# Precision_Singleboard_Charlieplex.net
KiCad netlist of a schematic drawn in EAGLE
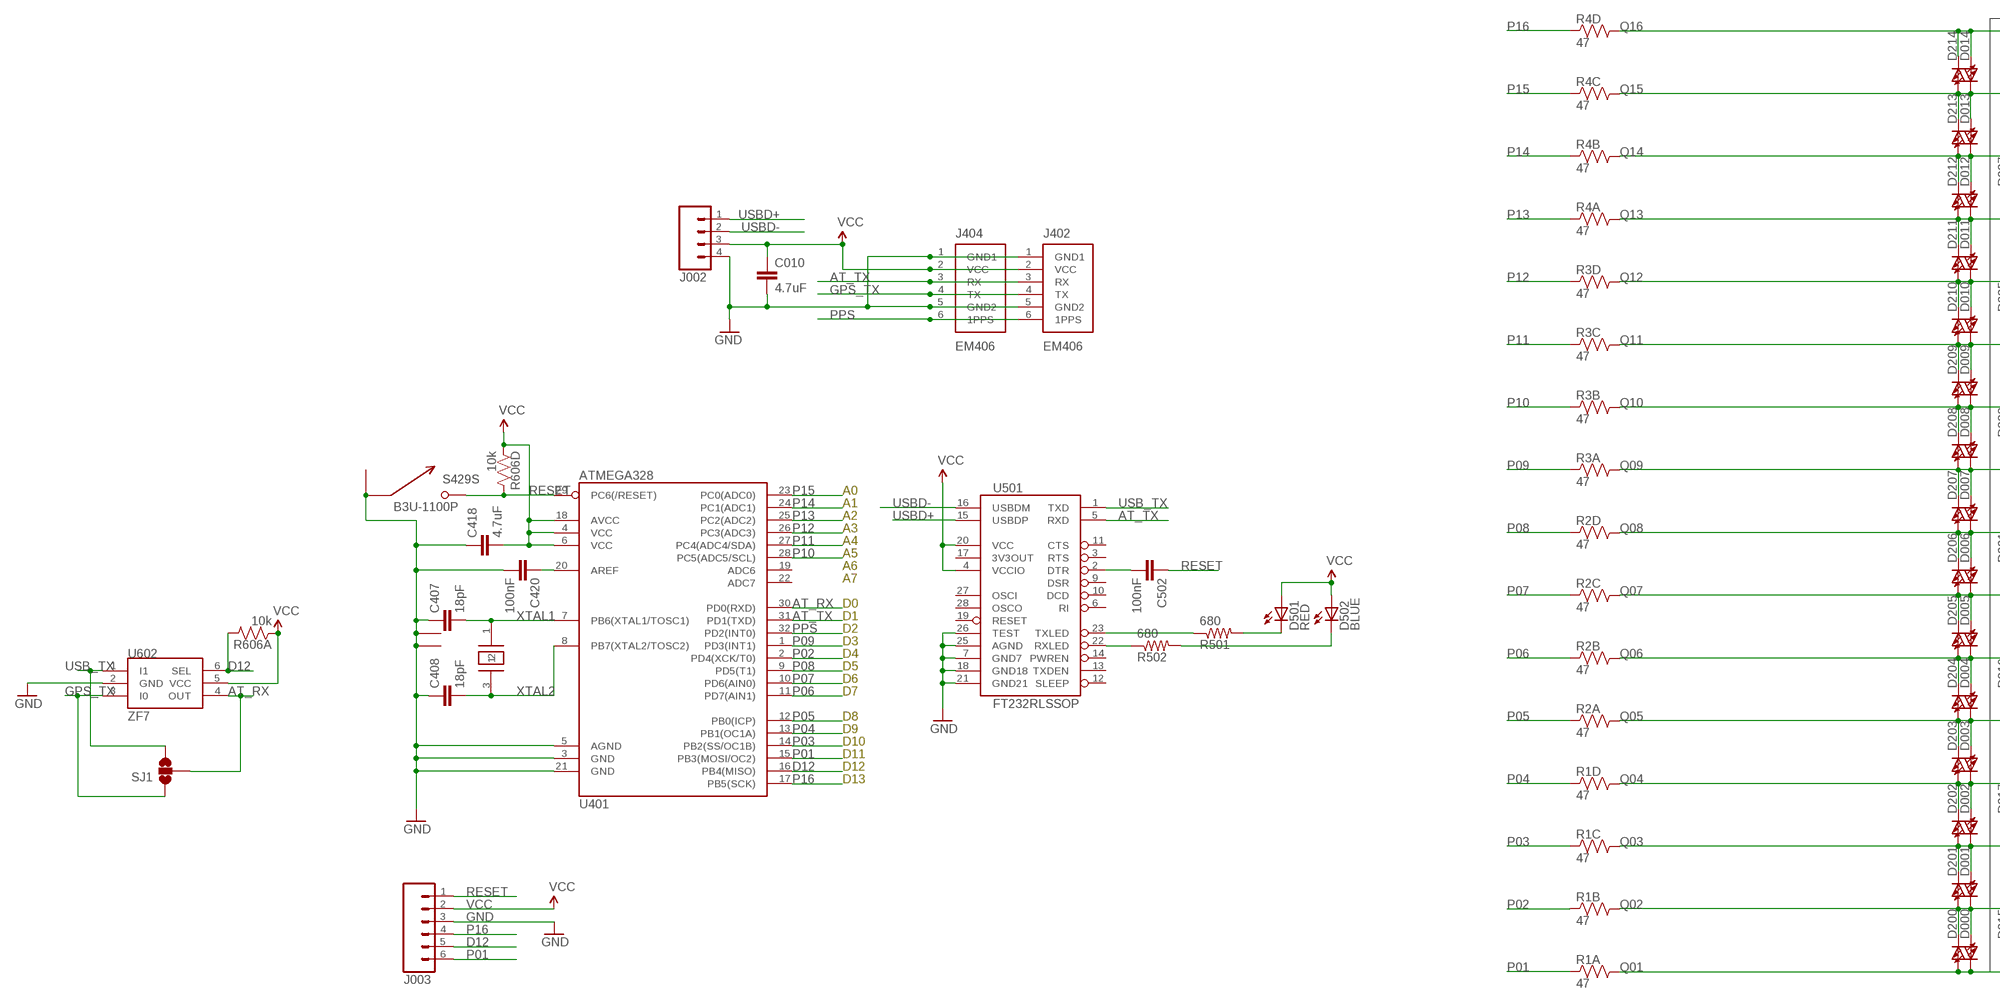
[diagram p0: schematic, sheet 1, part 1 of 2]
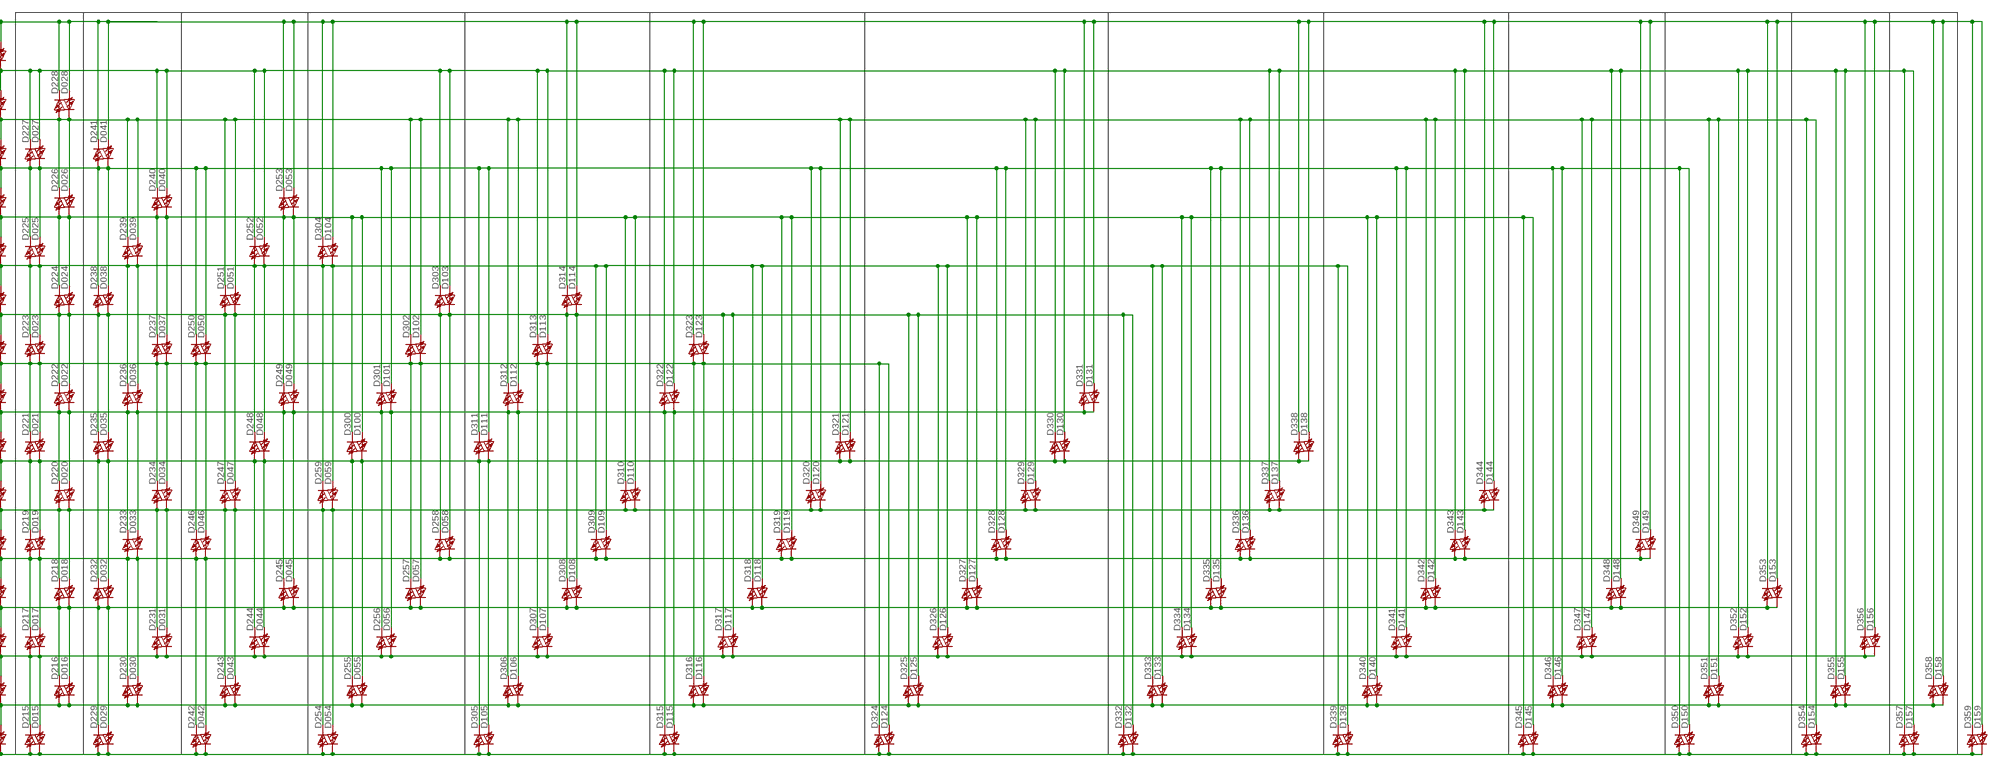
[diagram p1: schematic, sheet 1, part 2 of 2]

(export (version "E")
  (design (tool "Eeschema 10.0.6"))
  (components
    (comp (ref "C010")
      (value "4.7uF")
      (footprint "eagle-import:0603-CAP")
      (libsource (lib "eagle-import") (part "CAP0603-CAP"))
    )
    (comp (ref "C407")
      (value "18pF")
      (footprint "eagle-import:0603-CAP")
      (libsource (lib "eagle-import") (part "CAP0603-CAP"))
    )
    (comp (ref "C408")
      (value "18pF")
      (footprint "eagle-import:0603-CAP")
      (libsource (lib "eagle-import") (part "CAP0603-CAP"))
    )
    (comp (ref "C418")
      (value "4.7uF")
      (footprint "eagle-import:0603-CAP")
      (libsource (lib "eagle-import") (part "CAP0603-CAP"))
    )
    (comp (ref "C420")
      (value "100nF")
      (footprint "eagle-import:0603-CAP")
      (libsource (lib "eagle-import") (part "CAP0603-CAP"))
    )
    (comp (ref "C502")
      (value "100nF")
      (footprint "eagle-import:0603-CAP")
      (libsource (lib "eagle-import") (part "CAP0603-CAP"))
    )
    (comp (ref "D000")
      (value "HOUR")
      (footprint "eagle-import:LED-0603")
      (libsource (lib "eagle-import") (part "LED0603"))
    )
    (comp (ref "D001")
      (value "HOUR")
      (footprint "eagle-import:LED-0603")
      (libsource (lib "eagle-import") (part "LED0603"))
    )
    (comp (ref "D002")
      (value "HOUR")
      (footprint "eagle-import:LED-0603")
      (libsource (lib "eagle-import") (part "LED0603"))
    )
    (comp (ref "D003")
      (value "HOUR")
      (footprint "eagle-import:LED-0603")
      (libsource (lib "eagle-import") (part "LED0603"))
    )
    (comp (ref "D004")
      (value "HOUR")
      (footprint "eagle-import:LED-0603")
      (libsource (lib "eagle-import") (part "LED0603"))
    )
    (comp (ref "D005")
      (value "HOUR")
      (footprint "eagle-import:LED-0603")
      (libsource (lib "eagle-import") (part "LED0603"))
    )
    (comp (ref "D006")
      (value "HOUR")
      (footprint "eagle-import:LED-0603")
      (libsource (lib "eagle-import") (part "LED0603"))
    )
    (comp (ref "D007")
      (value "HOUR")
      (footprint "eagle-import:LED-0603")
      (libsource (lib "eagle-import") (part "LED0603"))
    )
    (comp (ref "D008")
      (value "HOUR")
      (footprint "eagle-import:LED-0603")
      (libsource (lib "eagle-import") (part "LED0603"))
    )
    (comp (ref "D009")
      (value "HOUR")
      (footprint "eagle-import:LED-0603")
      (libsource (lib "eagle-import") (part "LED0603"))
    )
    (comp (ref "D010")
      (value "HOUR")
      (footprint "eagle-import:LED-0603")
      (libsource (lib "eagle-import") (part "LED0603"))
    )
    (comp (ref "D011")
      (value "HOUR")
      (footprint "eagle-import:LED-0603")
      (libsource (lib "eagle-import") (part "LED0603"))
    )
    (comp (ref "D012")
      (value "HOUR")
      (footprint "eagle-import:LED-0603")
      (libsource (lib "eagle-import") (part "LED0603"))
    )
    (comp (ref "D013")
      (value "HOUR")
      (footprint "eagle-import:LED-0603")
      (libsource (lib "eagle-import") (part "LED0603"))
    )
    (comp (ref "D014")
      (value "HOUR")
      (footprint "eagle-import:LED-0603")
      (libsource (lib "eagle-import") (part "LED0603"))
    )
    (comp (ref "D015")
      (value "HOUR")
      (footprint "eagle-import:LED-0603")
      (libsource (lib "eagle-import") (part "LED0603"))
    )
    (comp (ref "D016")
      (value "HOUR")
      (footprint "eagle-import:LED-0603")
      (libsource (lib "eagle-import") (part "LED0603"))
    )
    (comp (ref "D017")
      (value "HOUR")
      (footprint "eagle-import:LED-0603")
      (libsource (lib "eagle-import") (part "LED0603"))
    )
    (comp (ref "D018")
      (value "HOUR")
      (footprint "eagle-import:LED-0603")
      (libsource (lib "eagle-import") (part "LED0603"))
    )
    (comp (ref "D019")
      (value "HOUR")
      (footprint "eagle-import:LED-0603")
      (libsource (lib "eagle-import") (part "LED0603"))
    )
    (comp (ref "D020")
      (value "HOUR")
      (footprint "eagle-import:LED-0603")
      (libsource (lib "eagle-import") (part "LED0603"))
    )
    (comp (ref "D021")
      (value "HOUR")
      (footprint "eagle-import:LED-0603")
      (libsource (lib "eagle-import") (part "LED0603"))
    )
    (comp (ref "D022")
      (value "HOUR")
      (footprint "eagle-import:LED-0603")
      (libsource (lib "eagle-import") (part "LED0603"))
    )
    (comp (ref "D023")
      (value "HOUR")
      (footprint "eagle-import:LED-0603")
      (libsource (lib "eagle-import") (part "LED0603"))
    )
    (comp (ref "D024")
      (value "HOUR")
      (footprint "eagle-import:LED-0603")
      (libsource (lib "eagle-import") (part "LED0603"))
    )
    (comp (ref "D025")
      (value "HOUR")
      (footprint "eagle-import:LED-0603")
      (libsource (lib "eagle-import") (part "LED0603"))
    )
    (comp (ref "D026")
      (value "HOUR")
      (footprint "eagle-import:LED-0603")
      (libsource (lib "eagle-import") (part "LED0603"))
    )
    (comp (ref "D027")
      (value "HOUR")
      (footprint "eagle-import:LED-0603")
      (libsource (lib "eagle-import") (part "LED0603"))
    )
    (comp (ref "D028")
      (value "HOUR")
      (footprint "eagle-import:LED-0603")
      (libsource (lib "eagle-import") (part "LED0603"))
    )
    (comp (ref "D029")
      (value "HOUR")
      (footprint "eagle-import:LED-0603")
      (libsource (lib "eagle-import") (part "LED0603"))
    )
    (comp (ref "D030")
      (value "HOUR")
      (footprint "eagle-import:LED-0603")
      (libsource (lib "eagle-import") (part "LED0603"))
    )
    (comp (ref "D031")
      (value "HOUR")
      (footprint "eagle-import:LED-0603")
      (libsource (lib "eagle-import") (part "LED0603"))
    )
    (comp (ref "D032")
      (value "HOUR")
      (footprint "eagle-import:LED-0603")
      (libsource (lib "eagle-import") (part "LED0603"))
    )
    (comp (ref "D033")
      (value "HOUR")
      (footprint "eagle-import:LED-0603")
      (libsource (lib "eagle-import") (part "LED0603"))
    )
    (comp (ref "D034")
      (value "HOUR")
      (footprint "eagle-import:LED-0603")
      (libsource (lib "eagle-import") (part "LED0603"))
    )
    (comp (ref "D035")
      (value "HOUR")
      (footprint "eagle-import:LED-0603")
      (libsource (lib "eagle-import") (part "LED0603"))
    )
    (comp (ref "D036")
      (value "HOUR")
      (footprint "eagle-import:LED-0603")
      (libsource (lib "eagle-import") (part "LED0603"))
    )
    (comp (ref "D037")
      (value "HOUR")
      (footprint "eagle-import:LED-0603")
      (libsource (lib "eagle-import") (part "LED0603"))
    )
    (comp (ref "D038")
      (value "HOUR")
      (footprint "eagle-import:LED-0603")
      (libsource (lib "eagle-import") (part "LED0603"))
    )
    (comp (ref "D039")
      (value "HOUR")
      (footprint "eagle-import:LED-0603")
      (libsource (lib "eagle-import") (part "LED0603"))
    )
    (comp (ref "D040")
      (value "HOUR")
      (footprint "eagle-import:LED-0603")
      (libsource (lib "eagle-import") (part "LED0603"))
    )
    (comp (ref "D041")
      (value "HOUR")
      (footprint "eagle-import:LED-0603")
      (libsource (lib "eagle-import") (part "LED0603"))
    )
    (comp (ref "D042")
      (value "HOUR")
      (footprint "eagle-import:LED-0603")
      (libsource (lib "eagle-import") (part "LED0603"))
    )
    (comp (ref "D043")
      (value "HOUR")
      (footprint "eagle-import:LED-0603")
      (libsource (lib "eagle-import") (part "LED0603"))
    )
    (comp (ref "D044")
      (value "HOUR")
      (footprint "eagle-import:LED-0603")
      (libsource (lib "eagle-import") (part "LED0603"))
    )
    (comp (ref "D045")
      (value "HOUR")
      (footprint "eagle-import:LED-0603")
      (libsource (lib "eagle-import") (part "LED0603"))
    )
    (comp (ref "D046")
      (value "HOUR")
      (footprint "eagle-import:LED-0603")
      (libsource (lib "eagle-import") (part "LED0603"))
    )
    (comp (ref "D047")
      (value "HOUR")
      (footprint "eagle-import:LED-0603")
      (libsource (lib "eagle-import") (part "LED0603"))
    )
    (comp (ref "D048")
      (value "HOUR")
      (footprint "eagle-import:LED-0603")
      (libsource (lib "eagle-import") (part "LED0603"))
    )
    (comp (ref "D049")
      (value "HOUR")
      (footprint "eagle-import:LED-0603")
      (libsource (lib "eagle-import") (part "LED0603"))
    )
    (comp (ref "D050")
      (value "HOUR")
      (footprint "eagle-import:LED-0603")
      (libsource (lib "eagle-import") (part "LED0603"))
    )
    (comp (ref "D051")
      (value "HOUR")
      (footprint "eagle-import:LED-0603")
      (libsource (lib "eagle-import") (part "LED0603"))
    )
    (comp (ref "D052")
      (value "HOUR")
      (footprint "eagle-import:LED-0603")
      (libsource (lib "eagle-import") (part "LED0603"))
    )
    (comp (ref "D053")
      (value "HOUR")
      (footprint "eagle-import:LED-0603")
      (libsource (lib "eagle-import") (part "LED0603"))
    )
    (comp (ref "D054")
      (value "HOUR")
      (footprint "eagle-import:LED-0603")
      (libsource (lib "eagle-import") (part "LED0603"))
    )
    (comp (ref "D055")
      (value "HOUR")
      (footprint "eagle-import:LED-0603")
      (libsource (lib "eagle-import") (part "LED0603"))
    )
    (comp (ref "D056")
      (value "HOUR")
      (footprint "eagle-import:LED-0603")
      (libsource (lib "eagle-import") (part "LED0603"))
    )
    (comp (ref "D057")
      (value "HOUR")
      (footprint "eagle-import:LED-0603")
      (libsource (lib "eagle-import") (part "LED0603"))
    )
    (comp (ref "D058")
      (value "HOUR")
      (footprint "eagle-import:LED-0603")
      (libsource (lib "eagle-import") (part "LED0603"))
    )
    (comp (ref "D059")
      (value "HOUR")
      (footprint "eagle-import:LED-0603")
      (libsource (lib "eagle-import") (part "LED0603"))
    )
    (comp (ref "D100")
      (value "HOUR")
      (footprint "eagle-import:LED-0603")
      (libsource (lib "eagle-import") (part "LED0603"))
    )
    (comp (ref "D101")
      (value "HOUR")
      (footprint "eagle-import:LED-0603")
      (libsource (lib "eagle-import") (part "LED0603"))
    )
    (comp (ref "D102")
      (value "HOUR")
      (footprint "eagle-import:LED-0603")
      (libsource (lib "eagle-import") (part "LED0603"))
    )
    (comp (ref "D103")
      (value "HOUR")
      (footprint "eagle-import:LED-0603")
      (libsource (lib "eagle-import") (part "LED0603"))
    )
    (comp (ref "D104")
      (value "HOUR")
      (footprint "eagle-import:LED-0603")
      (libsource (lib "eagle-import") (part "LED0603"))
    )
    (comp (ref "D105")
      (value "HOUR")
      (footprint "eagle-import:LED-0603")
      (libsource (lib "eagle-import") (part "LED0603"))
    )
    (comp (ref "D106")
      (value "HOUR")
      (footprint "eagle-import:LED-0603")
      (libsource (lib "eagle-import") (part "LED0603"))
    )
    (comp (ref "D107")
      (value "HOUR")
      (footprint "eagle-import:LED-0603")
      (libsource (lib "eagle-import") (part "LED0603"))
    )
    (comp (ref "D108")
      (value "HOUR")
      (footprint "eagle-import:LED-0603")
      (libsource (lib "eagle-import") (part "LED0603"))
    )
    (comp (ref "D109")
      (value "HOUR")
      (footprint "eagle-import:LED-0603")
      (libsource (lib "eagle-import") (part "LED0603"))
    )
    (comp (ref "D110")
      (value "HOUR")
      (footprint "eagle-import:LED-0603")
      (libsource (lib "eagle-import") (part "LED0603"))
    )
    (comp (ref "D111")
      (value "HOUR")
      (footprint "eagle-import:LED-0603")
      (libsource (lib "eagle-import") (part "LED0603"))
    )
    (comp (ref "D112")
      (value "HOUR")
      (footprint "eagle-import:LED-0603")
      (libsource (lib "eagle-import") (part "LED0603"))
    )
    (comp (ref "D113")
      (value "HOUR")
      (footprint "eagle-import:LED-0603")
      (libsource (lib "eagle-import") (part "LED0603"))
    )
    (comp (ref "D114")
      (value "HOUR")
      (footprint "eagle-import:LED-0603")
      (libsource (lib "eagle-import") (part "LED0603"))
    )
    (comp (ref "D115")
      (value "HOUR")
      (footprint "eagle-import:LED-0603")
      (libsource (lib "eagle-import") (part "LED0603"))
    )
    (comp (ref "D116")
      (value "HOUR")
      (footprint "eagle-import:LED-0603")
      (libsource (lib "eagle-import") (part "LED0603"))
    )
    (comp (ref "D117")
      (value "HOUR")
      (footprint "eagle-import:LED-0603")
      (libsource (lib "eagle-import") (part "LED0603"))
    )
    (comp (ref "D118")
      (value "HOUR")
      (footprint "eagle-import:LED-0603")
      (libsource (lib "eagle-import") (part "LED0603"))
    )
    (comp (ref "D119")
      (value "HOUR")
      (footprint "eagle-import:LED-0603")
      (libsource (lib "eagle-import") (part "LED0603"))
    )
    (comp (ref "D120")
      (value "HOUR")
      (footprint "eagle-import:LED-0603")
      (libsource (lib "eagle-import") (part "LED0603"))
    )
    (comp (ref "D121")
      (value "HOUR")
      (footprint "eagle-import:LED-0603")
      (libsource (lib "eagle-import") (part "LED0603"))
    )
    (comp (ref "D122")
      (value "HOUR")
      (footprint "eagle-import:LED-0603")
      (libsource (lib "eagle-import") (part "LED0603"))
    )
    (comp (ref "D123")
      (value "HOUR")
      (footprint "eagle-import:LED-0603")
      (libsource (lib "eagle-import") (part "LED0603"))
    )
    (comp (ref "D124")
      (value "HOUR")
      (footprint "eagle-import:LED-0603")
      (libsource (lib "eagle-import") (part "LED0603"))
    )
    (comp (ref "D125")
      (value "HOUR")
      (footprint "eagle-import:LED-0603")
      (libsource (lib "eagle-import") (part "LED0603"))
    )
    (comp (ref "D126")
      (value "HOUR")
      (footprint "eagle-import:LED-0603")
      (libsource (lib "eagle-import") (part "LED0603"))
    )
    (comp (ref "D127")
      (value "HOUR")
      (footprint "eagle-import:LED-0603")
      (libsource (lib "eagle-import") (part "LED0603"))
    )
    (comp (ref "D128")
      (value "HOUR")
      (footprint "eagle-import:LED-0603")
      (libsource (lib "eagle-import") (part "LED0603"))
    )
    (comp (ref "D129")
      (value "HOUR")
      (footprint "eagle-import:LED-0603")
      (libsource (lib "eagle-import") (part "LED0603"))
    )
    (comp (ref "D130")
      (value "HOUR")
      (footprint "eagle-import:LED-0603")
      (libsource (lib "eagle-import") (part "LED0603"))
    )
    (comp (ref "D131")
      (value "HOUR")
      (footprint "eagle-import:LED-0603")
      (libsource (lib "eagle-import") (part "LED0603"))
    )
    (comp (ref "D132")
      (value "HOUR")
      (footprint "eagle-import:LED-0603")
      (libsource (lib "eagle-import") (part "LED0603"))
    )
    (comp (ref "D133")
      (value "HOUR")
      (footprint "eagle-import:LED-0603")
      (libsource (lib "eagle-import") (part "LED0603"))
    )
    (comp (ref "D134")
      (value "HOUR")
      (footprint "eagle-import:LED-0603")
      (libsource (lib "eagle-import") (part "LED0603"))
    )
    (comp (ref "D135")
      (value "HOUR")
      (footprint "eagle-import:LED-0603")
      (libsource (lib "eagle-import") (part "LED0603"))
    )
    (comp (ref "D136")
      (value "HOUR")
      (footprint "eagle-import:LED-0603")
      (libsource (lib "eagle-import") (part "LED0603"))
    )
    (comp (ref "D137")
      (value "HOUR")
      (footprint "eagle-import:LED-0603")
      (libsource (lib "eagle-import") (part "LED0603"))
    )
    (comp (ref "D138")
      (value "HOUR")
      (footprint "eagle-import:LED-0603")
      (libsource (lib "eagle-import") (part "LED0603"))
    )
    (comp (ref "D139")
      (value "HOUR")
      (footprint "eagle-import:LED-0603")
      (libsource (lib "eagle-import") (part "LED0603"))
    )
    (comp (ref "D140")
      (value "HOUR")
      (footprint "eagle-import:LED-0603")
      (libsource (lib "eagle-import") (part "LED0603"))
    )
    (comp (ref "D141")
      (value "HOUR")
      (footprint "eagle-import:LED-0603")
      (libsource (lib "eagle-import") (part "LED0603"))
    )
    (comp (ref "D142")
      (value "HOUR")
      (footprint "eagle-import:LED-0603")
      (libsource (lib "eagle-import") (part "LED0603"))
    )
    (comp (ref "D143")
      (value "HOUR")
      (footprint "eagle-import:LED-0603")
      (libsource (lib "eagle-import") (part "LED0603"))
    )
    (comp (ref "D144")
      (value "HOUR")
      (footprint "eagle-import:LED-0603")
      (libsource (lib "eagle-import") (part "LED0603"))
    )
    (comp (ref "D145")
      (value "HOUR")
      (footprint "eagle-import:LED-0603")
      (libsource (lib "eagle-import") (part "LED0603"))
    )
    (comp (ref "D146")
      (value "HOUR")
      (footprint "eagle-import:LED-0603")
      (libsource (lib "eagle-import") (part "LED0603"))
    )
    (comp (ref "D147")
      (value "HOUR")
      (footprint "eagle-import:LED-0603")
      (libsource (lib "eagle-import") (part "LED0603"))
    )
    (comp (ref "D148")
      (value "HOUR")
      (footprint "eagle-import:LED-0603")
      (libsource (lib "eagle-import") (part "LED0603"))
    )
    (comp (ref "D149")
      (value "HOUR")
      (footprint "eagle-import:LED-0603")
      (libsource (lib "eagle-import") (part "LED0603"))
    )
    (comp (ref "D150")
      (value "HOUR")
      (footprint "eagle-import:LED-0603")
      (libsource (lib "eagle-import") (part "LED0603"))
    )
    (comp (ref "D151")
      (value "HOUR")
      (footprint "eagle-import:LED-0603")
      (libsource (lib "eagle-import") (part "LED0603"))
    )
    (comp (ref "D152")
      (value "HOUR")
      (footprint "eagle-import:LED-0603")
      (libsource (lib "eagle-import") (part "LED0603"))
    )
    (comp (ref "D153")
      (value "HOUR")
      (footprint "eagle-import:LED-0603")
      (libsource (lib "eagle-import") (part "LED0603"))
    )
    (comp (ref "D154")
      (value "HOUR")
      (footprint "eagle-import:LED-0603")
      (libsource (lib "eagle-import") (part "LED0603"))
    )
    (comp (ref "D155")
      (value "HOUR")
      (footprint "eagle-import:LED-0603")
      (libsource (lib "eagle-import") (part "LED0603"))
    )
    (comp (ref "D156")
      (value "HOUR")
      (footprint "eagle-import:LED-0603")
      (libsource (lib "eagle-import") (part "LED0603"))
    )
    (comp (ref "D157")
      (value "HOUR")
      (footprint "eagle-import:LED-0603")
      (libsource (lib "eagle-import") (part "LED0603"))
    )
    (comp (ref "D158")
      (value "HOUR")
      (footprint "eagle-import:LED-0603")
      (libsource (lib "eagle-import") (part "LED0603"))
    )
    (comp (ref "D159")
      (value "HOUR")
      (footprint "eagle-import:LED-0603")
      (libsource (lib "eagle-import") (part "LED0603"))
    )
    (comp (ref "D200")
      (value "HOUR")
      (footprint "eagle-import:LED-0603")
      (libsource (lib "eagle-import") (part "LED0603"))
    )
    (comp (ref "D201")
      (value "HOUR")
      (footprint "eagle-import:LED-0603")
      (libsource (lib "eagle-import") (part "LED0603"))
    )
    (comp (ref "D202")
      (value "HOUR")
      (footprint "eagle-import:LED-0603")
      (libsource (lib "eagle-import") (part "LED0603"))
    )
    (comp (ref "D203")
      (value "HOUR")
      (footprint "eagle-import:LED-0603")
      (libsource (lib "eagle-import") (part "LED0603"))
    )
    (comp (ref "D204")
      (value "HOUR")
      (footprint "eagle-import:LED-0603")
      (libsource (lib "eagle-import") (part "LED0603"))
    )
    (comp (ref "D205")
      (value "HOUR")
      (footprint "eagle-import:LED-0603")
      (libsource (lib "eagle-import") (part "LED0603"))
    )
    (comp (ref "D206")
      (value "HOUR")
      (footprint "eagle-import:LED-0603")
      (libsource (lib "eagle-import") (part "LED0603"))
    )
    (comp (ref "D207")
      (value "HOUR")
      (footprint "eagle-import:LED-0603")
      (libsource (lib "eagle-import") (part "LED0603"))
    )
    (comp (ref "D208")
      (value "HOUR")
      (footprint "eagle-import:LED-0603")
      (libsource (lib "eagle-import") (part "LED0603"))
    )
    (comp (ref "D209")
      (value "HOUR")
      (footprint "eagle-import:LED-0603")
      (libsource (lib "eagle-import") (part "LED0603"))
    )
    (comp (ref "D210")
      (value "HOUR")
      (footprint "eagle-import:LED-0603")
      (libsource (lib "eagle-import") (part "LED0603"))
    )
    (comp (ref "D211")
      (value "HOUR")
      (footprint "eagle-import:LED-0603")
      (libsource (lib "eagle-import") (part "LED0603"))
    )
    (comp (ref "D212")
      (value "HOUR")
      (footprint "eagle-import:LED-0603")
      (libsource (lib "eagle-import") (part "LED0603"))
    )
    (comp (ref "D213")
      (value "HOUR")
      (footprint "eagle-import:LED-0603")
      (libsource (lib "eagle-import") (part "LED0603"))
    )
    (comp (ref "D214")
      (value "HOUR")
      (footprint "eagle-import:LED-0603")
      (libsource (lib "eagle-import") (part "LED0603"))
    )
    (comp (ref "D215")
      (value "HOUR")
      (footprint "eagle-import:LED-0603")
      (libsource (lib "eagle-import") (part "LED0603"))
    )
    (comp (ref "D216")
      (value "HOUR")
      (footprint "eagle-import:LED-0603")
      (libsource (lib "eagle-import") (part "LED0603"))
    )
    (comp (ref "D217")
      (value "HOUR")
      (footprint "eagle-import:LED-0603")
      (libsource (lib "eagle-import") (part "LED0603"))
    )
    (comp (ref "D218")
      (value "HOUR")
      (footprint "eagle-import:LED-0603")
      (libsource (lib "eagle-import") (part "LED0603"))
    )
    (comp (ref "D219")
      (value "HOUR")
      (footprint "eagle-import:LED-0603")
      (libsource (lib "eagle-import") (part "LED0603"))
    )
    (comp (ref "D220")
      (value "HOUR")
      (footprint "eagle-import:LED-0603")
      (libsource (lib "eagle-import") (part "LED0603"))
    )
    (comp (ref "D221")
      (value "HOUR")
      (footprint "eagle-import:LED-0603")
      (libsource (lib "eagle-import") (part "LED0603"))
    )
    (comp (ref "D222")
      (value "HOUR")
      (footprint "eagle-import:LED-0603")
      (libsource (lib "eagle-import") (part "LED0603"))
    )
    (comp (ref "D223")
      (value "HOUR")
      (footprint "eagle-import:LED-0603")
      (libsource (lib "eagle-import") (part "LED0603"))
    )
    (comp (ref "D224")
      (value "HOUR")
      (footprint "eagle-import:LED-0603")
      (libsource (lib "eagle-import") (part "LED0603"))
    )
    (comp (ref "D225")
      (value "HOUR")
      (footprint "eagle-import:LED-0603")
      (libsource (lib "eagle-import") (part "LED0603"))
    )
    (comp (ref "D226")
      (value "HOUR")
      (footprint "eagle-import:LED-0603")
      (libsource (lib "eagle-import") (part "LED0603"))
    )
    (comp (ref "D227")
      (value "HOUR")
      (footprint "eagle-import:LED-0603")
      (libsource (lib "eagle-import") (part "LED0603"))
    )
    (comp (ref "D228")
      (value "HOUR")
      (footprint "eagle-import:LED-0603")
      (libsource (lib "eagle-import") (part "LED0603"))
    )
    (comp (ref "D229")
      (value "HOUR")
      (footprint "eagle-import:LED-0603")
      (libsource (lib "eagle-import") (part "LED0603"))
    )
    (comp (ref "D230")
      (value "HOUR")
      (footprint "eagle-import:LED-0603")
      (libsource (lib "eagle-import") (part "LED0603"))
    )
    (comp (ref "D231")
      (value "HOUR")
      (footprint "eagle-import:LED-0603")
      (libsource (lib "eagle-import") (part "LED0603"))
    )
    (comp (ref "D232")
      (value "HOUR")
      (footprint "eagle-import:LED-0603")
      (libsource (lib "eagle-import") (part "LED0603"))
    )
    (comp (ref "D233")
      (value "HOUR")
      (footprint "eagle-import:LED-0603")
      (libsource (lib "eagle-import") (part "LED0603"))
    )
    (comp (ref "D234")
      (value "HOUR")
      (footprint "eagle-import:LED-0603")
      (libsource (lib "eagle-import") (part "LED0603"))
    )
    (comp (ref "D235")
      (value "HOUR")
      (footprint "eagle-import:LED-0603")
      (libsource (lib "eagle-import") (part "LED0603"))
    )
    (comp (ref "D236")
      (value "HOUR")
      (footprint "eagle-import:LED-0603")
      (libsource (lib "eagle-import") (part "LED0603"))
    )
    (comp (ref "D237")
      (value "HOUR")
      (footprint "eagle-import:LED-0603")
      (libsource (lib "eagle-import") (part "LED0603"))
    )
    (comp (ref "D238")
      (value "HOUR")
      (footprint "eagle-import:LED-0603")
      (libsource (lib "eagle-import") (part "LED0603"))
    )
    (comp (ref "D239")
      (value "HOUR")
      (footprint "eagle-import:LED-0603")
      (libsource (lib "eagle-import") (part "LED0603"))
    )
    (comp (ref "D240")
      (value "HOUR")
      (footprint "eagle-import:LED-0603")
      (libsource (lib "eagle-import") (part "LED0603"))
    )
    (comp (ref "D241")
      (value "HOUR")
      (footprint "eagle-import:LED-0603")
      (libsource (lib "eagle-import") (part "LED0603"))
    )
    (comp (ref "D242")
      (value "HOUR")
      (footprint "eagle-import:LED-0603")
      (libsource (lib "eagle-import") (part "LED0603"))
    )
    (comp (ref "D243")
      (value "HOUR")
      (footprint "eagle-import:LED-0603")
      (libsource (lib "eagle-import") (part "LED0603"))
    )
    (comp (ref "D244")
      (value "HOUR")
      (footprint "eagle-import:LED-0603")
      (libsource (lib "eagle-import") (part "LED0603"))
    )
    (comp (ref "D245")
      (value "HOUR")
      (footprint "eagle-import:LED-0603")
      (libsource (lib "eagle-import") (part "LED0603"))
    )
    (comp (ref "D246")
      (value "HOUR")
      (footprint "eagle-import:LED-0603")
      (libsource (lib "eagle-import") (part "LED0603"))
    )
    (comp (ref "D247")
      (value "HOUR")
      (footprint "eagle-import:LED-0603")
      (libsource (lib "eagle-import") (part "LED0603"))
    )
    (comp (ref "D248")
      (value "HOUR")
      (footprint "eagle-import:LED-0603")
      (libsource (lib "eagle-import") (part "LED0603"))
    )
    (comp (ref "D249")
      (value "HOUR")
      (footprint "eagle-import:LED-0603")
      (libsource (lib "eagle-import") (part "LED0603"))
    )
    (comp (ref "D250")
      (value "HOUR")
      (footprint "eagle-import:LED-0603")
      (libsource (lib "eagle-import") (part "LED0603"))
    )
    (comp (ref "D251")
      (value "HOUR")
      (footprint "eagle-import:LED-0603")
      (libsource (lib "eagle-import") (part "LED0603"))
    )
    (comp (ref "D252")
      (value "HOUR")
      (footprint "eagle-import:LED-0603")
      (libsource (lib "eagle-import") (part "LED0603"))
    )
    (comp (ref "D253")
      (value "HOUR")
      (footprint "eagle-import:LED-0603")
      (libsource (lib "eagle-import") (part "LED0603"))
    )
    (comp (ref "D254")
      (value "HOUR")
      (footprint "eagle-import:LED-0603")
      (libsource (lib "eagle-import") (part "LED0603"))
    )
    (comp (ref "D255")
      (value "HOUR")
      (footprint "eagle-import:LED-0603")
      (libsource (lib "eagle-import") (part "LED0603"))
    )
    (comp (ref "D256")
      (value "HOUR")
      (footprint "eagle-import:LED-0603")
      (libsource (lib "eagle-import") (part "LED0603"))
    )
    (comp (ref "D257")
      (value "HOUR")
      (footprint "eagle-import:LED-0603")
      (libsource (lib "eagle-import") (part "LED0603"))
    )
    (comp (ref "D258")
      (value "HOUR")
      (footprint "eagle-import:LED-0603")
      (libsource (lib "eagle-import") (part "LED0603"))
    )
    (comp (ref "D259")
      (value "HOUR")
      (footprint "eagle-import:LED-0603")
      (libsource (lib "eagle-import") (part "LED0603"))
    )
    (comp (ref "D300")
      (value "HOUR")
      (footprint "eagle-import:LED-0603")
      (libsource (lib "eagle-import") (part "LED0603"))
    )
    (comp (ref "D301")
      (value "HOUR")
      (footprint "eagle-import:LED-0603")
      (libsource (lib "eagle-import") (part "LED0603"))
    )
    (comp (ref "D302")
      (value "HOUR")
      (footprint "eagle-import:LED-0603")
      (libsource (lib "eagle-import") (part "LED0603"))
    )
    (comp (ref "D303")
      (value "HOUR")
      (footprint "eagle-import:LED-0603")
      (libsource (lib "eagle-import") (part "LED0603"))
    )
    (comp (ref "D304")
      (value "HOUR")
      (footprint "eagle-import:LED-0603")
      (libsource (lib "eagle-import") (part "LED0603"))
    )
    (comp (ref "D305")
      (value "HOUR")
      (footprint "eagle-import:LED-0603")
      (libsource (lib "eagle-import") (part "LED0603"))
    )
    (comp (ref "D306")
      (value "HOUR")
      (footprint "eagle-import:LED-0603")
      (libsource (lib "eagle-import") (part "LED0603"))
    )
    (comp (ref "D307")
      (value "HOUR")
      (footprint "eagle-import:LED-0603")
      (libsource (lib "eagle-import") (part "LED0603"))
    )
    (comp (ref "D308")
      (value "HOUR")
      (footprint "eagle-import:LED-0603")
      (libsource (lib "eagle-import") (part "LED0603"))
    )
    (comp (ref "D309")
      (value "HOUR")
      (footprint "eagle-import:LED-0603")
      (libsource (lib "eagle-import") (part "LED0603"))
    )
    (comp (ref "D310")
      (value "HOUR")
      (footprint "eagle-import:LED-0603")
      (libsource (lib "eagle-import") (part "LED0603"))
    )
    (comp (ref "D311")
      (value "HOUR")
      (footprint "eagle-import:LED-0603")
      (libsource (lib "eagle-import") (part "LED0603"))
    )
    (comp (ref "D312")
      (value "HOUR")
      (footprint "eagle-import:LED-0603")
      (libsource (lib "eagle-import") (part "LED0603"))
    )
    (comp (ref "D313")
      (value "HOUR")
      (footprint "eagle-import:LED-0603")
      (libsource (lib "eagle-import") (part "LED0603"))
    )
    (comp (ref "D314")
      (value "HOUR")
      (footprint "eagle-import:LED-0603")
      (libsource (lib "eagle-import") (part "LED0603"))
    )
    (comp (ref "D315")
      (value "HOUR")
      (footprint "eagle-import:LED-0603")
      (libsource (lib "eagle-import") (part "LED0603"))
    )
    (comp (ref "D316")
      (value "HOUR")
      (footprint "eagle-import:LED-0603")
      (libsource (lib "eagle-import") (part "LED0603"))
    )
    (comp (ref "D317")
      (value "HOUR")
      (footprint "eagle-import:LED-0603")
      (libsource (lib "eagle-import") (part "LED0603"))
    )
    (comp (ref "D318")
      (value "HOUR")
      (footprint "eagle-import:LED-0603")
      (libsource (lib "eagle-import") (part "LED0603"))
    )
    (comp (ref "D319")
      (value "HOUR")
      (footprint "eagle-import:LED-0603")
      (libsource (lib "eagle-import") (part "LED0603"))
    )
    (comp (ref "D320")
      (value "HOUR")
      (footprint "eagle-import:LED-0603")
      (libsource (lib "eagle-import") (part "LED0603"))
    )
    (comp (ref "D321")
      (value "HOUR")
      (footprint "eagle-import:LED-0603")
      (libsource (lib "eagle-import") (part "LED0603"))
    )
    (comp (ref "D322")
      (value "HOUR")
      (footprint "eagle-import:LED-0603")
      (libsource (lib "eagle-import") (part "LED0603"))
    )
    (comp (ref "D323")
      (value "HOUR")
      (footprint "eagle-import:LED-0603")
      (libsource (lib "eagle-import") (part "LED0603"))
    )
    (comp (ref "D324")
      (value "HOUR")
      (footprint "eagle-import:LED-0603")
      (libsource (lib "eagle-import") (part "LED0603"))
    )
    (comp (ref "D325")
      (value "HOUR")
      (footprint "eagle-import:LED-0603")
      (libsource (lib "eagle-import") (part "LED0603"))
    )
    (comp (ref "D326")
      (value "HOUR")
      (footprint "eagle-import:LED-0603")
      (libsource (lib "eagle-import") (part "LED0603"))
    )
    (comp (ref "D327")
      (value "HOUR")
      (footprint "eagle-import:LED-0603")
      (libsource (lib "eagle-import") (part "LED0603"))
    )
    (comp (ref "D328")
      (value "HOUR")
      (footprint "eagle-import:LED-0603")
      (libsource (lib "eagle-import") (part "LED0603"))
    )
    (comp (ref "D329")
      (value "HOUR")
      (footprint "eagle-import:LED-0603")
      (libsource (lib "eagle-import") (part "LED0603"))
    )
    (comp (ref "D330")
      (value "HOUR")
      (footprint "eagle-import:LED-0603")
      (libsource (lib "eagle-import") (part "LED0603"))
    )
    (comp (ref "D331")
      (value "HOUR")
      (footprint "eagle-import:LED-0603")
      (libsource (lib "eagle-import") (part "LED0603"))
    )
    (comp (ref "D332")
      (value "HOUR")
      (footprint "eagle-import:LED-0603")
      (libsource (lib "eagle-import") (part "LED0603"))
    )
    (comp (ref "D333")
      (value "HOUR")
      (footprint "eagle-import:LED-0603")
      (libsource (lib "eagle-import") (part "LED0603"))
    )
    (comp (ref "D334")
      (value "HOUR")
      (footprint "eagle-import:LED-0603")
      (libsource (lib "eagle-import") (part "LED0603"))
    )
    (comp (ref "D335")
      (value "HOUR")
      (footprint "eagle-import:LED-0603")
      (libsource (lib "eagle-import") (part "LED0603"))
    )
    (comp (ref "D336")
      (value "HOUR")
      (footprint "eagle-import:LED-0603")
      (libsource (lib "eagle-import") (part "LED0603"))
    )
    (comp (ref "D337")
      (value "HOUR")
      (footprint "eagle-import:LED-0603")
      (libsource (lib "eagle-import") (part "LED0603"))
    )
    (comp (ref "D338")
      (value "HOUR")
      (footprint "eagle-import:LED-0603")
      (libsource (lib "eagle-import") (part "LED0603"))
    )
    (comp (ref "D339")
      (value "HOUR")
      (footprint "eagle-import:LED-0603")
      (libsource (lib "eagle-import") (part "LED0603"))
    )
    (comp (ref "D340")
      (value "HOUR")
      (footprint "eagle-import:LED-0603")
      (libsource (lib "eagle-import") (part "LED0603"))
    )
    (comp (ref "D341")
      (value "HOUR")
      (footprint "eagle-import:LED-0603")
      (libsource (lib "eagle-import") (part "LED0603"))
    )
    (comp (ref "D342")
      (value "HOUR")
      (footprint "eagle-import:LED-0603")
      (libsource (lib "eagle-import") (part "LED0603"))
    )
    (comp (ref "D343")
      (value "HOUR")
      (footprint "eagle-import:LED-0603")
      (libsource (lib "eagle-import") (part "LED0603"))
    )
    (comp (ref "D344")
      (value "HOUR")
      (footprint "eagle-import:LED-0603")
      (libsource (lib "eagle-import") (part "LED0603"))
    )
    (comp (ref "D345")
      (value "HOUR")
      (footprint "eagle-import:LED-0603")
      (libsource (lib "eagle-import") (part "LED0603"))
    )
    (comp (ref "D346")
      (value "HOUR")
      (footprint "eagle-import:LED-0603")
      (libsource (lib "eagle-import") (part "LED0603"))
    )
    (comp (ref "D347")
      (value "HOUR")
      (footprint "eagle-import:LED-0603")
      (libsource (lib "eagle-import") (part "LED0603"))
    )
    (comp (ref "D348")
      (value "HOUR")
      (footprint "eagle-import:LED-0603")
      (libsource (lib "eagle-import") (part "LED0603"))
    )
    (comp (ref "D349")
      (value "HOUR")
      (footprint "eagle-import:LED-0603")
      (libsource (lib "eagle-import") (part "LED0603"))
    )
    (comp (ref "D350")
      (value "HOUR")
      (footprint "eagle-import:LED-0603")
      (libsource (lib "eagle-import") (part "LED0603"))
    )
    (comp (ref "D351")
      (value "HOUR")
      (footprint "eagle-import:LED-0603")
      (libsource (lib "eagle-import") (part "LED0603"))
    )
    (comp (ref "D352")
      (value "HOUR")
      (footprint "eagle-import:LED-0603")
      (libsource (lib "eagle-import") (part "LED0603"))
    )
    (comp (ref "D353")
      (value "HOUR")
      (footprint "eagle-import:LED-0603")
      (libsource (lib "eagle-import") (part "LED0603"))
    )
    (comp (ref "D354")
      (value "HOUR")
      (footprint "eagle-import:LED-0603")
      (libsource (lib "eagle-import") (part "LED0603"))
    )
    (comp (ref "D355")
      (value "HOUR")
      (footprint "eagle-import:LED-0603")
      (libsource (lib "eagle-import") (part "LED0603"))
    )
    (comp (ref "D356")
      (value "HOUR")
      (footprint "eagle-import:LED-0603")
      (libsource (lib "eagle-import") (part "LED0603"))
    )
    (comp (ref "D357")
      (value "HOUR")
      (footprint "eagle-import:LED-0603")
      (libsource (lib "eagle-import") (part "LED0603"))
    )
    (comp (ref "D358")
      (value "HOUR")
      (footprint "eagle-import:LED-0603")
      (libsource (lib "eagle-import") (part "LED0603"))
    )
    (comp (ref "D359")
      (value "HOUR")
      (footprint "eagle-import:LED-0603")
      (libsource (lib "eagle-import") (part "LED0603"))
    )
    (comp (ref "D501")
      (value "RED")
      (footprint "eagle-import:LED-0603")
      (libsource (lib "eagle-import") (part "LED0603"))
    )
    (comp (ref "D502")
      (value "BLUE")
      (footprint "eagle-import:LED-0603")
      (libsource (lib "eagle-import") (part "LED0603"))
    )
    (comp (ref "J002")
      (value "M04PTH")
      (footprint "eagle-import:1X04")
      (libsource (lib "eagle-import") (part "M04PTH"))
    )
    (comp (ref "J003")
      (value "M06SIP")
      (footprint "eagle-import:1X06")
      (libsource (lib "eagle-import") (part "M06SIP"))
    )
    (comp (ref "J402")
      (value "EM406")
      (footprint "eagle-import:EM406")
      (libsource (lib "eagle-import") (part "EM406"))
    )
    (comp (ref "J404")
      (value "EM406")
      (footprint "eagle-import:EM406")
      (libsource (lib "eagle-import") (part "EM406"))
    )
    (comp (ref "R1")
      (value "47")
      (footprint "eagle-import:CRA04")
      (libsource (lib "eagle-import") (part "RP404"))
    )
    (comp (ref "R2")
      (value "47")
      (footprint "eagle-import:CRA04")
      (libsource (lib "eagle-import") (part "RP404"))
    )
    (comp (ref "R3")
      (value "47")
      (footprint "eagle-import:CRA04")
      (libsource (lib "eagle-import") (part "RP404"))
    )
    (comp (ref "R4")
      (value "47")
      (footprint "eagle-import:CRA04")
      (libsource (lib "eagle-import") (part "RP404"))
    )
    (comp (ref "R501")
      (value "680")
      (footprint "eagle-import:0603-RES")
      (libsource (lib "eagle-import") (part "RESISTOR0603-RES"))
    )
    (comp (ref "R502")
      (value "680")
      (footprint "eagle-import:0603-RES")
      (libsource (lib "eagle-import") (part "RESISTOR0603-RES"))
    )
    (comp (ref "R606")
      (value "10k")
      (footprint "eagle-import:CRA04")
      (libsource (lib "eagle-import") (part "RP404"))
    )
    (comp (ref "S429")
      (value "B3U-1100P")
      (footprint "eagle-import:B3U-1100P")
      (libsource (lib "eagle-import") (part "B3U-1100P"))
    )
    (comp (ref "SJ1")
      (value "SOLDERJUMPER_2WAYS")
      (footprint "eagle-import:SJ_3")
      (libsource (lib "eagle-import") (part "SOLDERJUMPER_2WAYS"))
    )
    (comp (ref "U401")
      (value "ATMEGA328")
      (footprint "eagle-import:TQFP32-08")
      (libsource (lib "eagle-import") (part "ATMEGA168"))
    )
    (comp (ref "U501")
      (value "FT232RLSSOP")
      (footprint "eagle-import:SSOP28DB")
      (libsource (lib "eagle-import") (part "FT232RLSSOP"))
    )
    (comp (ref "U602")
      (value "ZF7")
      (footprint "eagle-import:SC-70-6")
      (libsource (lib "eagle-import") (part "NC7SZ157"))
    )
    (comp (ref "Y401")
      (value "12.00")
      (footprint "eagle-import:CRYSTAL_SMD")
      (libsource (lib "eagle-import") (part "TSX-3225"))
    )
  )
  (nets
    (net (code "1") (name "/AT_RX") (class "Default")
      (node (ref "SJ1") (pin "2") (pinfunction "2_2") (pintype "passive"))
      (node (ref "U401") (pin "30") (pinfunction "PD0(RXD)_30") (pintype "bidirectional"))
      (node (ref "U602") (pin "4") (pinfunction "OUT_4") (pintype "bidirectional"))
    )
    (net (code "2") (name "/AT_TX") (class "Default")
      (node (ref "J402") (pin "3") (pinfunction "RX_3") (pintype "bidirectional"))
      (node (ref "J404") (pin "3") (pinfunction "RX_3") (pintype "bidirectional"))
      (node (ref "U401") (pin "31") (pinfunction "PD1(TXD)_31") (pintype "bidirectional"))
      (node (ref "U501") (pin "5") (pinfunction "RXD_5") (pintype "input"))
    )
    (net (code "3") (name "/D12") (class "Default")
      (node (ref "J003") (pin "5") (pinfunction "5_5") (pintype "passive"))
      (node (ref "R606") (pin "8") (pinfunction "2_8") (pintype "passive"))
      (node (ref "U401") (pin "16") (pinfunction "PB4(MISO)_16") (pintype "bidirectional"))
      (node (ref "U602") (pin "6") (pinfunction "SEL_6") (pintype "bidirectional"))
    )
    (net (code "4") (name "/GPS_TX") (class "Default")
      (node (ref "J402") (pin "4") (pinfunction "TX_4") (pintype "bidirectional"))
      (node (ref "J404") (pin "4") (pinfunction "TX_4") (pintype "bidirectional"))
      (node (ref "SJ1") (pin "1") (pinfunction "1_1") (pintype "passive"))
      (node (ref "U602") (pin "3") (pinfunction "I0_3") (pintype "bidirectional"))
    )
    (net (code "5") (name "/P01") (class "Default")
      (node (ref "J003") (pin "6") (pinfunction "6_6") (pintype "passive"))
      (node (ref "R1") (pin "1") (pinfunction "1_1") (pintype "passive"))
      (node (ref "U401") (pin "15") (pinfunction "PB3(MOSI/OC2)_15") (pintype "bidirectional"))
    )
    (net (code "6") (name "/P02") (class "Default")
      (node (ref "R1") (pin "2") (pinfunction "1_2") (pintype "passive"))
      (node (ref "U401") (pin "2") (pinfunction "PD4(XCK/T0)_2") (pintype "bidirectional"))
    )
    (net (code "7") (name "/P03") (class "Default")
      (node (ref "R1") (pin "3") (pinfunction "1_3") (pintype "passive"))
      (node (ref "U401") (pin "14") (pinfunction "PB2(SS/OC1B)_14") (pintype "bidirectional"))
    )
    (net (code "8") (name "/P04") (class "Default")
      (node (ref "R1") (pin "4") (pinfunction "1_4") (pintype "passive"))
      (node (ref "U401") (pin "13") (pinfunction "PB1(OC1A)_13") (pintype "bidirectional"))
    )
    (net (code "9") (name "/P05") (class "Default")
      (node (ref "R2") (pin "1") (pinfunction "1_1") (pintype "passive"))
      (node (ref "U401") (pin "12") (pinfunction "PB0(ICP)_12") (pintype "bidirectional"))
    )
    (net (code "10") (name "/P06") (class "Default")
      (node (ref "R2") (pin "2") (pinfunction "1_2") (pintype "passive"))
      (node (ref "U401") (pin "11") (pinfunction "PD7(AIN1)_11") (pintype "bidirectional"))
    )
    (net (code "11") (name "/P07") (class "Default")
      (node (ref "R2") (pin "3") (pinfunction "1_3") (pintype "passive"))
      (node (ref "U401") (pin "10") (pinfunction "PD6(AIN0)_10") (pintype "bidirectional"))
    )
    (net (code "12") (name "/P08") (class "Default")
      (node (ref "R2") (pin "4") (pinfunction "1_4") (pintype "passive"))
      (node (ref "U401") (pin "9") (pinfunction "PD5(T1)_9") (pintype "bidirectional"))
    )
    (net (code "13") (name "/P09") (class "Default")
      (node (ref "R3") (pin "1") (pinfunction "1_1") (pintype "passive"))
      (node (ref "U401") (pin "1") (pinfunction "PD3(INT1)_1") (pintype "bidirectional"))
    )
    (net (code "14") (name "/P10") (class "Default")
      (node (ref "R3") (pin "2") (pinfunction "1_2") (pintype "passive"))
      (node (ref "U401") (pin "28") (pinfunction "PC5(ADC5/SCL)_28") (pintype "bidirectional"))
    )
    (net (code "15") (name "/P11") (class "Default")
      (node (ref "R3") (pin "3") (pinfunction "1_3") (pintype "passive"))
      (node (ref "U401") (pin "27") (pinfunction "PC4(ADC4/SDA)_27") (pintype "bidirectional"))
    )
    (net (code "16") (name "/P12") (class "Default")
      (node (ref "R3") (pin "4") (pinfunction "1_4") (pintype "passive"))
      (node (ref "U401") (pin "26") (pinfunction "PC3(ADC3)_26") (pintype "bidirectional"))
    )
    (net (code "17") (name "/P13") (class "Default")
      (node (ref "R4") (pin "1") (pinfunction "1_1") (pintype "passive"))
      (node (ref "U401") (pin "25") (pinfunction "PC2(ADC2)_25") (pintype "bidirectional"))
    )
    (net (code "18") (name "/P14") (class "Default")
      (node (ref "R4") (pin "2") (pinfunction "1_2") (pintype "passive"))
      (node (ref "U401") (pin "24") (pinfunction "PC1(ADC1)_24") (pintype "bidirectional"))
    )
    (net (code "19") (name "/P15") (class "Default")
      (node (ref "R4") (pin "3") (pinfunction "1_3") (pintype "passive"))
      (node (ref "U401") (pin "23") (pinfunction "PC0(ADC0)_23") (pintype "bidirectional"))
    )
    (net (code "20") (name "/P16") (class "Default")
      (node (ref "J003") (pin "4") (pinfunction "4_4") (pintype "passive"))
      (node (ref "R4") (pin "4") (pinfunction "1_4") (pintype "passive"))
      (node (ref "U401") (pin "17") (pinfunction "PB5(SCK)_17") (pintype "bidirectional"))
    )
    (net (code "21") (name "/PPS") (class "Default")
      (node (ref "J402") (pin "6") (pinfunction "1PPS_6") (pintype "bidirectional"))
      (node (ref "J404") (pin "6") (pinfunction "1PPS_6") (pintype "bidirectional"))
      (node (ref "U401") (pin "32") (pinfunction "PD2(INT0)_32") (pintype "bidirectional"))
    )
    (net (code "22") (name "/Q01") (class "Default")
      (node (ref "D000") (pin "C") (pinfunction "C_C") (pintype "passive"))
      (node (ref "D015") (pin "C") (pinfunction "C_C") (pintype "passive"))
      (node (ref "D029") (pin "C") (pinfunction "C_C") (pintype "passive"))
      (node (ref "D042") (pin "C") (pinfunction "C_C") (pintype "passive"))
      (node (ref "D054") (pin "C") (pinfunction "C_C") (pintype "passive"))
      (node (ref "D105") (pin "C") (pinfunction "C_C") (pintype "passive"))
      (node (ref "D115") (pin "C") (pinfunction "C_C") (pintype "passive"))
      (node (ref "D124") (pin "C") (pinfunction "C_C") (pintype "passive"))
      (node (ref "D132") (pin "C") (pinfunction "C_C") (pintype "passive"))
      (node (ref "D139") (pin "C") (pinfunction "C_C") (pintype "passive"))
      (node (ref "D145") (pin "C") (pinfunction "C_C") (pintype "passive"))
      (node (ref "D150") (pin "C") (pinfunction "C_C") (pintype "passive"))
      (node (ref "D154") (pin "C") (pinfunction "C_C") (pintype "passive"))
      (node (ref "D157") (pin "C") (pinfunction "C_C") (pintype "passive"))
      (node (ref "D159") (pin "C") (pinfunction "C_C") (pintype "passive"))
      (node (ref "D200") (pin "A") (pinfunction "A_A") (pintype "passive"))
      (node (ref "D215") (pin "A") (pinfunction "A_A") (pintype "passive"))
      (node (ref "D229") (pin "A") (pinfunction "A_A") (pintype "passive"))
      (node (ref "D242") (pin "A") (pinfunction "A_A") (pintype "passive"))
      (node (ref "D254") (pin "A") (pinfunction "A_A") (pintype "passive"))
      (node (ref "D305") (pin "A") (pinfunction "A_A") (pintype "passive"))
      (node (ref "D315") (pin "A") (pinfunction "A_A") (pintype "passive"))
      (node (ref "D324") (pin "A") (pinfunction "A_A") (pintype "passive"))
      (node (ref "D332") (pin "A") (pinfunction "A_A") (pintype "passive"))
      (node (ref "D339") (pin "A") (pinfunction "A_A") (pintype "passive"))
      (node (ref "D345") (pin "A") (pinfunction "A_A") (pintype "passive"))
      (node (ref "D350") (pin "A") (pinfunction "A_A") (pintype "passive"))
      (node (ref "D354") (pin "A") (pinfunction "A_A") (pintype "passive"))
      (node (ref "D357") (pin "A") (pinfunction "A_A") (pintype "passive"))
      (node (ref "D359") (pin "A") (pinfunction "A_A") (pintype "passive"))
      (node (ref "R1") (pin "8") (pinfunction "2_8") (pintype "passive"))
    )
    (net (code "23") (name "/Q02") (class "Default")
      (node (ref "D000") (pin "A") (pinfunction "A_A") (pintype "passive"))
      (node (ref "D001") (pin "C") (pinfunction "C_C") (pintype "passive"))
      (node (ref "D016") (pin "C") (pinfunction "C_C") (pintype "passive"))
      (node (ref "D030") (pin "C") (pinfunction "C_C") (pintype "passive"))
      (node (ref "D043") (pin "C") (pinfunction "C_C") (pintype "passive"))
      (node (ref "D055") (pin "C") (pinfunction "C_C") (pintype "passive"))
      (node (ref "D106") (pin "C") (pinfunction "C_C") (pintype "passive"))
      (node (ref "D116") (pin "C") (pinfunction "C_C") (pintype "passive"))
      (node (ref "D125") (pin "C") (pinfunction "C_C") (pintype "passive"))
      (node (ref "D133") (pin "C") (pinfunction "C_C") (pintype "passive"))
      (node (ref "D140") (pin "C") (pinfunction "C_C") (pintype "passive"))
      (node (ref "D146") (pin "C") (pinfunction "C_C") (pintype "passive"))
      (node (ref "D151") (pin "C") (pinfunction "C_C") (pintype "passive"))
      (node (ref "D155") (pin "C") (pinfunction "C_C") (pintype "passive"))
      (node (ref "D158") (pin "C") (pinfunction "C_C") (pintype "passive"))
      (node (ref "D200") (pin "C") (pinfunction "C_C") (pintype "passive"))
      (node (ref "D201") (pin "A") (pinfunction "A_A") (pintype "passive"))
      (node (ref "D216") (pin "A") (pinfunction "A_A") (pintype "passive"))
      (node (ref "D230") (pin "A") (pinfunction "A_A") (pintype "passive"))
      (node (ref "D243") (pin "A") (pinfunction "A_A") (pintype "passive"))
      (node (ref "D255") (pin "A") (pinfunction "A_A") (pintype "passive"))
      (node (ref "D306") (pin "A") (pinfunction "A_A") (pintype "passive"))
      (node (ref "D316") (pin "A") (pinfunction "A_A") (pintype "passive"))
      (node (ref "D325") (pin "A") (pinfunction "A_A") (pintype "passive"))
      (node (ref "D333") (pin "A") (pinfunction "A_A") (pintype "passive"))
      (node (ref "D340") (pin "A") (pinfunction "A_A") (pintype "passive"))
      (node (ref "D346") (pin "A") (pinfunction "A_A") (pintype "passive"))
      (node (ref "D351") (pin "A") (pinfunction "A_A") (pintype "passive"))
      (node (ref "D355") (pin "A") (pinfunction "A_A") (pintype "passive"))
      (node (ref "D358") (pin "A") (pinfunction "A_A") (pintype "passive"))
      (node (ref "R1") (pin "7") (pinfunction "2_7") (pintype "passive"))
    )
    (net (code "24") (name "/Q03") (class "Default")
      (node (ref "D001") (pin "A") (pinfunction "A_A") (pintype "passive"))
      (node (ref "D002") (pin "C") (pinfunction "C_C") (pintype "passive"))
      (node (ref "D015") (pin "A") (pinfunction "A_A") (pintype "passive"))
      (node (ref "D017") (pin "C") (pinfunction "C_C") (pintype "passive"))
      (node (ref "D031") (pin "C") (pinfunction "C_C") (pintype "passive"))
      (node (ref "D044") (pin "C") (pinfunction "C_C") (pintype "passive"))
      (node (ref "D056") (pin "C") (pinfunction "C_C") (pintype "passive"))
      (node (ref "D107") (pin "C") (pinfunction "C_C") (pintype "passive"))
      (node (ref "D117") (pin "C") (pinfunction "C_C") (pintype "passive"))
      (node (ref "D126") (pin "C") (pinfunction "C_C") (pintype "passive"))
      (node (ref "D134") (pin "C") (pinfunction "C_C") (pintype "passive"))
      (node (ref "D141") (pin "C") (pinfunction "C_C") (pintype "passive"))
      (node (ref "D147") (pin "C") (pinfunction "C_C") (pintype "passive"))
      (node (ref "D152") (pin "C") (pinfunction "C_C") (pintype "passive"))
      (node (ref "D156") (pin "C") (pinfunction "C_C") (pintype "passive"))
      (node (ref "D201") (pin "C") (pinfunction "C_C") (pintype "passive"))
      (node (ref "D202") (pin "A") (pinfunction "A_A") (pintype "passive"))
      (node (ref "D215") (pin "C") (pinfunction "C_C") (pintype "passive"))
      (node (ref "D217") (pin "A") (pinfunction "A_A") (pintype "passive"))
      (node (ref "D231") (pin "A") (pinfunction "A_A") (pintype "passive"))
      (node (ref "D244") (pin "A") (pinfunction "A_A") (pintype "passive"))
      (node (ref "D256") (pin "A") (pinfunction "A_A") (pintype "passive"))
      (node (ref "D307") (pin "A") (pinfunction "A_A") (pintype "passive"))
      (node (ref "D317") (pin "A") (pinfunction "A_A") (pintype "passive"))
      (node (ref "D326") (pin "A") (pinfunction "A_A") (pintype "passive"))
      (node (ref "D334") (pin "A") (pinfunction "A_A") (pintype "passive"))
      (node (ref "D341") (pin "A") (pinfunction "A_A") (pintype "passive"))
      (node (ref "D347") (pin "A") (pinfunction "A_A") (pintype "passive"))
      (node (ref "D352") (pin "A") (pinfunction "A_A") (pintype "passive"))
      (node (ref "D356") (pin "A") (pinfunction "A_A") (pintype "passive"))
      (node (ref "R1") (pin "6") (pinfunction "2_6") (pintype "passive"))
    )
    (net (code "25") (name "/Q04") (class "Default")
      (node (ref "D002") (pin "A") (pinfunction "A_A") (pintype "passive"))
      (node (ref "D003") (pin "C") (pinfunction "C_C") (pintype "passive"))
      (node (ref "D016") (pin "A") (pinfunction "A_A") (pintype "passive"))
      (node (ref "D018") (pin "C") (pinfunction "C_C") (pintype "passive"))
      (node (ref "D029") (pin "A") (pinfunction "A_A") (pintype "passive"))
      (node (ref "D032") (pin "C") (pinfunction "C_C") (pintype "passive"))
      (node (ref "D045") (pin "C") (pinfunction "C_C") (pintype "passive"))
      (node (ref "D057") (pin "C") (pinfunction "C_C") (pintype "passive"))
      (node (ref "D108") (pin "C") (pinfunction "C_C") (pintype "passive"))
      (node (ref "D118") (pin "C") (pinfunction "C_C") (pintype "passive"))
      (node (ref "D127") (pin "C") (pinfunction "C_C") (pintype "passive"))
      (node (ref "D135") (pin "C") (pinfunction "C_C") (pintype "passive"))
      (node (ref "D142") (pin "C") (pinfunction "C_C") (pintype "passive"))
      (node (ref "D148") (pin "C") (pinfunction "C_C") (pintype "passive"))
      (node (ref "D153") (pin "C") (pinfunction "C_C") (pintype "passive"))
      (node (ref "D202") (pin "C") (pinfunction "C_C") (pintype "passive"))
      (node (ref "D203") (pin "A") (pinfunction "A_A") (pintype "passive"))
      (node (ref "D216") (pin "C") (pinfunction "C_C") (pintype "passive"))
      (node (ref "D218") (pin "A") (pinfunction "A_A") (pintype "passive"))
      (node (ref "D229") (pin "C") (pinfunction "C_C") (pintype "passive"))
      (node (ref "D232") (pin "A") (pinfunction "A_A") (pintype "passive"))
      (node (ref "D245") (pin "A") (pinfunction "A_A") (pintype "passive"))
      (node (ref "D257") (pin "A") (pinfunction "A_A") (pintype "passive"))
      (node (ref "D308") (pin "A") (pinfunction "A_A") (pintype "passive"))
      (node (ref "D318") (pin "A") (pinfunction "A_A") (pintype "passive"))
      (node (ref "D327") (pin "A") (pinfunction "A_A") (pintype "passive"))
      (node (ref "D335") (pin "A") (pinfunction "A_A") (pintype "passive"))
      (node (ref "D342") (pin "A") (pinfunction "A_A") (pintype "passive"))
      (node (ref "D348") (pin "A") (pinfunction "A_A") (pintype "passive"))
      (node (ref "D353") (pin "A") (pinfunction "A_A") (pintype "passive"))
      (node (ref "R1") (pin "5") (pinfunction "2_5") (pintype "passive"))
    )
    (net (code "26") (name "/Q05") (class "Default")
      (node (ref "D003") (pin "A") (pinfunction "A_A") (pintype "passive"))
      (node (ref "D004") (pin "C") (pinfunction "C_C") (pintype "passive"))
      (node (ref "D017") (pin "A") (pinfunction "A_A") (pintype "passive"))
      (node (ref "D019") (pin "C") (pinfunction "C_C") (pintype "passive"))
      (node (ref "D030") (pin "A") (pinfunction "A_A") (pintype "passive"))
      (node (ref "D033") (pin "C") (pinfunction "C_C") (pintype "passive"))
      (node (ref "D042") (pin "A") (pinfunction "A_A") (pintype "passive"))
      (node (ref "D046") (pin "C") (pinfunction "C_C") (pintype "passive"))
      (node (ref "D058") (pin "C") (pinfunction "C_C") (pintype "passive"))
      (node (ref "D109") (pin "C") (pinfunction "C_C") (pintype "passive"))
      (node (ref "D119") (pin "C") (pinfunction "C_C") (pintype "passive"))
      (node (ref "D128") (pin "C") (pinfunction "C_C") (pintype "passive"))
      (node (ref "D136") (pin "C") (pinfunction "C_C") (pintype "passive"))
      (node (ref "D143") (pin "C") (pinfunction "C_C") (pintype "passive"))
      (node (ref "D149") (pin "C") (pinfunction "C_C") (pintype "passive"))
      (node (ref "D203") (pin "C") (pinfunction "C_C") (pintype "passive"))
      (node (ref "D204") (pin "A") (pinfunction "A_A") (pintype "passive"))
      (node (ref "D217") (pin "C") (pinfunction "C_C") (pintype "passive"))
      (node (ref "D219") (pin "A") (pinfunction "A_A") (pintype "passive"))
      (node (ref "D230") (pin "C") (pinfunction "C_C") (pintype "passive"))
      (node (ref "D233") (pin "A") (pinfunction "A_A") (pintype "passive"))
      (node (ref "D242") (pin "C") (pinfunction "C_C") (pintype "passive"))
      (node (ref "D246") (pin "A") (pinfunction "A_A") (pintype "passive"))
      (node (ref "D258") (pin "A") (pinfunction "A_A") (pintype "passive"))
      (node (ref "D309") (pin "A") (pinfunction "A_A") (pintype "passive"))
      (node (ref "D319") (pin "A") (pinfunction "A_A") (pintype "passive"))
      (node (ref "D328") (pin "A") (pinfunction "A_A") (pintype "passive"))
      (node (ref "D336") (pin "A") (pinfunction "A_A") (pintype "passive"))
      (node (ref "D343") (pin "A") (pinfunction "A_A") (pintype "passive"))
      (node (ref "D349") (pin "A") (pinfunction "A_A") (pintype "passive"))
      (node (ref "R2") (pin "8") (pinfunction "2_8") (pintype "passive"))
    )
    (net (code "27") (name "/Q06") (class "Default")
      (node (ref "D004") (pin "A") (pinfunction "A_A") (pintype "passive"))
      (node (ref "D005") (pin "C") (pinfunction "C_C") (pintype "passive"))
      (node (ref "D018") (pin "A") (pinfunction "A_A") (pintype "passive"))
      (node (ref "D020") (pin "C") (pinfunction "C_C") (pintype "passive"))
      (node (ref "D031") (pin "A") (pinfunction "A_A") (pintype "passive"))
      (node (ref "D034") (pin "C") (pinfunction "C_C") (pintype "passive"))
      (node (ref "D043") (pin "A") (pinfunction "A_A") (pintype "passive"))
      (node (ref "D047") (pin "C") (pinfunction "C_C") (pintype "passive"))
      (node (ref "D054") (pin "A") (pinfunction "A_A") (pintype "passive"))
      (node (ref "D059") (pin "C") (pinfunction "C_C") (pintype "passive"))
      (node (ref "D110") (pin "C") (pinfunction "C_C") (pintype "passive"))
      (node (ref "D120") (pin "C") (pinfunction "C_C") (pintype "passive"))
      (node (ref "D129") (pin "C") (pinfunction "C_C") (pintype "passive"))
      (node (ref "D137") (pin "C") (pinfunction "C_C") (pintype "passive"))
      (node (ref "D144") (pin "C") (pinfunction "C_C") (pintype "passive"))
      (node (ref "D204") (pin "C") (pinfunction "C_C") (pintype "passive"))
      (node (ref "D205") (pin "A") (pinfunction "A_A") (pintype "passive"))
      (node (ref "D218") (pin "C") (pinfunction "C_C") (pintype "passive"))
      (node (ref "D220") (pin "A") (pinfunction "A_A") (pintype "passive"))
      (node (ref "D231") (pin "C") (pinfunction "C_C") (pintype "passive"))
      (node (ref "D234") (pin "A") (pinfunction "A_A") (pintype "passive"))
      (node (ref "D243") (pin "C") (pinfunction "C_C") (pintype "passive"))
      (node (ref "D247") (pin "A") (pinfunction "A_A") (pintype "passive"))
      (node (ref "D254") (pin "C") (pinfunction "C_C") (pintype "passive"))
      (node (ref "D259") (pin "A") (pinfunction "A_A") (pintype "passive"))
      (node (ref "D310") (pin "A") (pinfunction "A_A") (pintype "passive"))
      (node (ref "D320") (pin "A") (pinfunction "A_A") (pintype "passive"))
      (node (ref "D329") (pin "A") (pinfunction "A_A") (pintype "passive"))
      (node (ref "D337") (pin "A") (pinfunction "A_A") (pintype "passive"))
      (node (ref "D344") (pin "A") (pinfunction "A_A") (pintype "passive"))
      (node (ref "R2") (pin "7") (pinfunction "2_7") (pintype "passive"))
    )
    (net (code "28") (name "/Q07") (class "Default")
      (node (ref "D005") (pin "A") (pinfunction "A_A") (pintype "passive"))
      (node (ref "D006") (pin "C") (pinfunction "C_C") (pintype "passive"))
      (node (ref "D019") (pin "A") (pinfunction "A_A") (pintype "passive"))
      (node (ref "D021") (pin "C") (pinfunction "C_C") (pintype "passive"))
      (node (ref "D032") (pin "A") (pinfunction "A_A") (pintype "passive"))
      (node (ref "D035") (pin "C") (pinfunction "C_C") (pintype "passive"))
      (node (ref "D044") (pin "A") (pinfunction "A_A") (pintype "passive"))
      (node (ref "D048") (pin "C") (pinfunction "C_C") (pintype "passive"))
      (node (ref "D055") (pin "A") (pinfunction "A_A") (pintype "passive"))
      (node (ref "D100") (pin "C") (pinfunction "C_C") (pintype "passive"))
      (node (ref "D105") (pin "A") (pinfunction "A_A") (pintype "passive"))
      (node (ref "D111") (pin "C") (pinfunction "C_C") (pintype "passive"))
      (node (ref "D121") (pin "C") (pinfunction "C_C") (pintype "passive"))
      (node (ref "D130") (pin "C") (pinfunction "C_C") (pintype "passive"))
      (node (ref "D138") (pin "C") (pinfunction "C_C") (pintype "passive"))
      (node (ref "D205") (pin "C") (pinfunction "C_C") (pintype "passive"))
      (node (ref "D206") (pin "A") (pinfunction "A_A") (pintype "passive"))
      (node (ref "D219") (pin "C") (pinfunction "C_C") (pintype "passive"))
      (node (ref "D221") (pin "A") (pinfunction "A_A") (pintype "passive"))
      (node (ref "D232") (pin "C") (pinfunction "C_C") (pintype "passive"))
      (node (ref "D235") (pin "A") (pinfunction "A_A") (pintype "passive"))
      (node (ref "D244") (pin "C") (pinfunction "C_C") (pintype "passive"))
      (node (ref "D248") (pin "A") (pinfunction "A_A") (pintype "passive"))
      (node (ref "D255") (pin "C") (pinfunction "C_C") (pintype "passive"))
      (node (ref "D300") (pin "A") (pinfunction "A_A") (pintype "passive"))
      (node (ref "D305") (pin "C") (pinfunction "C_C") (pintype "passive"))
      (node (ref "D311") (pin "A") (pinfunction "A_A") (pintype "passive"))
      (node (ref "D321") (pin "A") (pinfunction "A_A") (pintype "passive"))
      (node (ref "D330") (pin "A") (pinfunction "A_A") (pintype "passive"))
      (node (ref "D338") (pin "A") (pinfunction "A_A") (pintype "passive"))
      (node (ref "R2") (pin "6") (pinfunction "2_6") (pintype "passive"))
    )
    (net (code "29") (name "/Q08") (class "Default")
      (node (ref "D006") (pin "A") (pinfunction "A_A") (pintype "passive"))
      (node (ref "D007") (pin "C") (pinfunction "C_C") (pintype "passive"))
      (node (ref "D020") (pin "A") (pinfunction "A_A") (pintype "passive"))
      (node (ref "D022") (pin "C") (pinfunction "C_C") (pintype "passive"))
      (node (ref "D033") (pin "A") (pinfunction "A_A") (pintype "passive"))
      (node (ref "D036") (pin "C") (pinfunction "C_C") (pintype "passive"))
      (node (ref "D045") (pin "A") (pinfunction "A_A") (pintype "passive"))
      (node (ref "D049") (pin "C") (pinfunction "C_C") (pintype "passive"))
      (node (ref "D056") (pin "A") (pinfunction "A_A") (pintype "passive"))
      (node (ref "D101") (pin "C") (pinfunction "C_C") (pintype "passive"))
      (node (ref "D106") (pin "A") (pinfunction "A_A") (pintype "passive"))
      (node (ref "D112") (pin "C") (pinfunction "C_C") (pintype "passive"))
      (node (ref "D115") (pin "A") (pinfunction "A_A") (pintype "passive"))
      (node (ref "D122") (pin "C") (pinfunction "C_C") (pintype "passive"))
      (node (ref "D131") (pin "C") (pinfunction "C_C") (pintype "passive"))
      (node (ref "D206") (pin "C") (pinfunction "C_C") (pintype "passive"))
      (node (ref "D207") (pin "A") (pinfunction "A_A") (pintype "passive"))
      (node (ref "D220") (pin "C") (pinfunction "C_C") (pintype "passive"))
      (node (ref "D222") (pin "A") (pinfunction "A_A") (pintype "passive"))
      (node (ref "D233") (pin "C") (pinfunction "C_C") (pintype "passive"))
      (node (ref "D236") (pin "A") (pinfunction "A_A") (pintype "passive"))
      (node (ref "D245") (pin "C") (pinfunction "C_C") (pintype "passive"))
      (node (ref "D249") (pin "A") (pinfunction "A_A") (pintype "passive"))
      (node (ref "D256") (pin "C") (pinfunction "C_C") (pintype "passive"))
      (node (ref "D301") (pin "A") (pinfunction "A_A") (pintype "passive"))
      (node (ref "D306") (pin "C") (pinfunction "C_C") (pintype "passive"))
      (node (ref "D312") (pin "A") (pinfunction "A_A") (pintype "passive"))
      (node (ref "D315") (pin "C") (pinfunction "C_C") (pintype "passive"))
      (node (ref "D322") (pin "A") (pinfunction "A_A") (pintype "passive"))
      (node (ref "D331") (pin "A") (pinfunction "A_A") (pintype "passive"))
      (node (ref "R2") (pin "5") (pinfunction "2_5") (pintype "passive"))
    )
    (net (code "30") (name "/Q09") (class "Default")
      (node (ref "D007") (pin "A") (pinfunction "A_A") (pintype "passive"))
      (node (ref "D008") (pin "C") (pinfunction "C_C") (pintype "passive"))
      (node (ref "D021") (pin "A") (pinfunction "A_A") (pintype "passive"))
      (node (ref "D023") (pin "C") (pinfunction "C_C") (pintype "passive"))
      (node (ref "D034") (pin "A") (pinfunction "A_A") (pintype "passive"))
      (node (ref "D037") (pin "C") (pinfunction "C_C") (pintype "passive"))
      (node (ref "D046") (pin "A") (pinfunction "A_A") (pintype "passive"))
      (node (ref "D050") (pin "C") (pinfunction "C_C") (pintype "passive"))
      (node (ref "D057") (pin "A") (pinfunction "A_A") (pintype "passive"))
      (node (ref "D102") (pin "C") (pinfunction "C_C") (pintype "passive"))
      (node (ref "D107") (pin "A") (pinfunction "A_A") (pintype "passive"))
      (node (ref "D113") (pin "C") (pinfunction "C_C") (pintype "passive"))
      (node (ref "D116") (pin "A") (pinfunction "A_A") (pintype "passive"))
      (node (ref "D123") (pin "C") (pinfunction "C_C") (pintype "passive"))
      (node (ref "D124") (pin "A") (pinfunction "A_A") (pintype "passive"))
      (node (ref "D207") (pin "C") (pinfunction "C_C") (pintype "passive"))
      (node (ref "D208") (pin "A") (pinfunction "A_A") (pintype "passive"))
      (node (ref "D221") (pin "C") (pinfunction "C_C") (pintype "passive"))
      (node (ref "D223") (pin "A") (pinfunction "A_A") (pintype "passive"))
      (node (ref "D234") (pin "C") (pinfunction "C_C") (pintype "passive"))
      (node (ref "D237") (pin "A") (pinfunction "A_A") (pintype "passive"))
      (node (ref "D246") (pin "C") (pinfunction "C_C") (pintype "passive"))
      (node (ref "D250") (pin "A") (pinfunction "A_A") (pintype "passive"))
      (node (ref "D257") (pin "C") (pinfunction "C_C") (pintype "passive"))
      (node (ref "D302") (pin "A") (pinfunction "A_A") (pintype "passive"))
      (node (ref "D307") (pin "C") (pinfunction "C_C") (pintype "passive"))
      (node (ref "D313") (pin "A") (pinfunction "A_A") (pintype "passive"))
      (node (ref "D316") (pin "C") (pinfunction "C_C") (pintype "passive"))
      (node (ref "D323") (pin "A") (pinfunction "A_A") (pintype "passive"))
      (node (ref "D324") (pin "C") (pinfunction "C_C") (pintype "passive"))
      (node (ref "R3") (pin "8") (pinfunction "2_8") (pintype "passive"))
    )
    (net (code "31") (name "/Q10") (class "Default")
      (node (ref "D008") (pin "A") (pinfunction "A_A") (pintype "passive"))
      (node (ref "D009") (pin "C") (pinfunction "C_C") (pintype "passive"))
      (node (ref "D022") (pin "A") (pinfunction "A_A") (pintype "passive"))
      (node (ref "D024") (pin "C") (pinfunction "C_C") (pintype "passive"))
      (node (ref "D035") (pin "A") (pinfunction "A_A") (pintype "passive"))
      (node (ref "D038") (pin "C") (pinfunction "C_C") (pintype "passive"))
      (node (ref "D047") (pin "A") (pinfunction "A_A") (pintype "passive"))
      (node (ref "D051") (pin "C") (pinfunction "C_C") (pintype "passive"))
      (node (ref "D058") (pin "A") (pinfunction "A_A") (pintype "passive"))
      (node (ref "D103") (pin "C") (pinfunction "C_C") (pintype "passive"))
      (node (ref "D108") (pin "A") (pinfunction "A_A") (pintype "passive"))
      (node (ref "D114") (pin "C") (pinfunction "C_C") (pintype "passive"))
      (node (ref "D117") (pin "A") (pinfunction "A_A") (pintype "passive"))
      (node (ref "D125") (pin "A") (pinfunction "A_A") (pintype "passive"))
      (node (ref "D132") (pin "A") (pinfunction "A_A") (pintype "passive"))
      (node (ref "D208") (pin "C") (pinfunction "C_C") (pintype "passive"))
      (node (ref "D209") (pin "A") (pinfunction "A_A") (pintype "passive"))
      (node (ref "D222") (pin "C") (pinfunction "C_C") (pintype "passive"))
      (node (ref "D224") (pin "A") (pinfunction "A_A") (pintype "passive"))
      (node (ref "D235") (pin "C") (pinfunction "C_C") (pintype "passive"))
      (node (ref "D238") (pin "A") (pinfunction "A_A") (pintype "passive"))
      (node (ref "D247") (pin "C") (pinfunction "C_C") (pintype "passive"))
      (node (ref "D251") (pin "A") (pinfunction "A_A") (pintype "passive"))
      (node (ref "D258") (pin "C") (pinfunction "C_C") (pintype "passive"))
      (node (ref "D303") (pin "A") (pinfunction "A_A") (pintype "passive"))
      (node (ref "D308") (pin "C") (pinfunction "C_C") (pintype "passive"))
      (node (ref "D314") (pin "A") (pinfunction "A_A") (pintype "passive"))
      (node (ref "D317") (pin "C") (pinfunction "C_C") (pintype "passive"))
      (node (ref "D325") (pin "C") (pinfunction "C_C") (pintype "passive"))
      (node (ref "D332") (pin "C") (pinfunction "C_C") (pintype "passive"))
      (node (ref "R3") (pin "7") (pinfunction "2_7") (pintype "passive"))
    )
    (net (code "32") (name "/Q11") (class "Default")
      (node (ref "D009") (pin "A") (pinfunction "A_A") (pintype "passive"))
      (node (ref "D010") (pin "C") (pinfunction "C_C") (pintype "passive"))
      (node (ref "D023") (pin "A") (pinfunction "A_A") (pintype "passive"))
      (node (ref "D025") (pin "C") (pinfunction "C_C") (pintype "passive"))
      (node (ref "D036") (pin "A") (pinfunction "A_A") (pintype "passive"))
      (node (ref "D039") (pin "C") (pinfunction "C_C") (pintype "passive"))
      (node (ref "D048") (pin "A") (pinfunction "A_A") (pintype "passive"))
      (node (ref "D052") (pin "C") (pinfunction "C_C") (pintype "passive"))
      (node (ref "D059") (pin "A") (pinfunction "A_A") (pintype "passive"))
      (node (ref "D104") (pin "C") (pinfunction "C_C") (pintype "passive"))
      (node (ref "D109") (pin "A") (pinfunction "A_A") (pintype "passive"))
      (node (ref "D118") (pin "A") (pinfunction "A_A") (pintype "passive"))
      (node (ref "D126") (pin "A") (pinfunction "A_A") (pintype "passive"))
      (node (ref "D133") (pin "A") (pinfunction "A_A") (pintype "passive"))
      (node (ref "D139") (pin "A") (pinfunction "A_A") (pintype "passive"))
      (node (ref "D209") (pin "C") (pinfunction "C_C") (pintype "passive"))
      (node (ref "D210") (pin "A") (pinfunction "A_A") (pintype "passive"))
      (node (ref "D223") (pin "C") (pinfunction "C_C") (pintype "passive"))
      (node (ref "D225") (pin "A") (pinfunction "A_A") (pintype "passive"))
      (node (ref "D236") (pin "C") (pinfunction "C_C") (pintype "passive"))
      (node (ref "D239") (pin "A") (pinfunction "A_A") (pintype "passive"))
      (node (ref "D248") (pin "C") (pinfunction "C_C") (pintype "passive"))
      (node (ref "D252") (pin "A") (pinfunction "A_A") (pintype "passive"))
      (node (ref "D259") (pin "C") (pinfunction "C_C") (pintype "passive"))
      (node (ref "D304") (pin "A") (pinfunction "A_A") (pintype "passive"))
      (node (ref "D309") (pin "C") (pinfunction "C_C") (pintype "passive"))
      (node (ref "D318") (pin "C") (pinfunction "C_C") (pintype "passive"))
      (node (ref "D326") (pin "C") (pinfunction "C_C") (pintype "passive"))
      (node (ref "D333") (pin "C") (pinfunction "C_C") (pintype "passive"))
      (node (ref "D339") (pin "C") (pinfunction "C_C") (pintype "passive"))
      (node (ref "R3") (pin "6") (pinfunction "2_6") (pintype "passive"))
    )
    (net (code "33") (name "/Q12") (class "Default")
      (node (ref "D010") (pin "A") (pinfunction "A_A") (pintype "passive"))
      (node (ref "D011") (pin "C") (pinfunction "C_C") (pintype "passive"))
      (node (ref "D024") (pin "A") (pinfunction "A_A") (pintype "passive"))
      (node (ref "D026") (pin "C") (pinfunction "C_C") (pintype "passive"))
      (node (ref "D037") (pin "A") (pinfunction "A_A") (pintype "passive"))
      (node (ref "D040") (pin "C") (pinfunction "C_C") (pintype "passive"))
      (node (ref "D049") (pin "A") (pinfunction "A_A") (pintype "passive"))
      (node (ref "D053") (pin "C") (pinfunction "C_C") (pintype "passive"))
      (node (ref "D100") (pin "A") (pinfunction "A_A") (pintype "passive"))
      (node (ref "D110") (pin "A") (pinfunction "A_A") (pintype "passive"))
      (node (ref "D119") (pin "A") (pinfunction "A_A") (pintype "passive"))
      (node (ref "D127") (pin "A") (pinfunction "A_A") (pintype "passive"))
      (node (ref "D134") (pin "A") (pinfunction "A_A") (pintype "passive"))
      (node (ref "D140") (pin "A") (pinfunction "A_A") (pintype "passive"))
      (node (ref "D145") (pin "A") (pinfunction "A_A") (pintype "passive"))
      (node (ref "D210") (pin "C") (pinfunction "C_C") (pintype "passive"))
      (node (ref "D211") (pin "A") (pinfunction "A_A") (pintype "passive"))
      (node (ref "D224") (pin "C") (pinfunction "C_C") (pintype "passive"))
      (node (ref "D226") (pin "A") (pinfunction "A_A") (pintype "passive"))
      (node (ref "D237") (pin "C") (pinfunction "C_C") (pintype "passive"))
      (node (ref "D240") (pin "A") (pinfunction "A_A") (pintype "passive"))
      (node (ref "D249") (pin "C") (pinfunction "C_C") (pintype "passive"))
      (node (ref "D253") (pin "A") (pinfunction "A_A") (pintype "passive"))
      (node (ref "D300") (pin "C") (pinfunction "C_C") (pintype "passive"))
      (node (ref "D310") (pin "C") (pinfunction "C_C") (pintype "passive"))
      (node (ref "D319") (pin "C") (pinfunction "C_C") (pintype "passive"))
      (node (ref "D327") (pin "C") (pinfunction "C_C") (pintype "passive"))
      (node (ref "D334") (pin "C") (pinfunction "C_C") (pintype "passive"))
      (node (ref "D340") (pin "C") (pinfunction "C_C") (pintype "passive"))
      (node (ref "D345") (pin "C") (pinfunction "C_C") (pintype "passive"))
      (node (ref "R3") (pin "5") (pinfunction "2_5") (pintype "passive"))
    )
    (net (code "34") (name "/Q13") (class "Default")
      (node (ref "D011") (pin "A") (pinfunction "A_A") (pintype "passive"))
      (node (ref "D012") (pin "C") (pinfunction "C_C") (pintype "passive"))
      (node (ref "D025") (pin "A") (pinfunction "A_A") (pintype "passive"))
      (node (ref "D027") (pin "C") (pinfunction "C_C") (pintype "passive"))
      (node (ref "D038") (pin "A") (pinfunction "A_A") (pintype "passive"))
      (node (ref "D041") (pin "C") (pinfunction "C_C") (pintype "passive"))
      (node (ref "D050") (pin "A") (pinfunction "A_A") (pintype "passive"))
      (node (ref "D101") (pin "A") (pinfunction "A_A") (pintype "passive"))
      (node (ref "D111") (pin "A") (pinfunction "A_A") (pintype "passive"))
      (node (ref "D120") (pin "A") (pinfunction "A_A") (pintype "passive"))
      (node (ref "D128") (pin "A") (pinfunction "A_A") (pintype "passive"))
      (node (ref "D135") (pin "A") (pinfunction "A_A") (pintype "passive"))
      (node (ref "D141") (pin "A") (pinfunction "A_A") (pintype "passive"))
      (node (ref "D146") (pin "A") (pinfunction "A_A") (pintype "passive"))
      (node (ref "D150") (pin "A") (pinfunction "A_A") (pintype "passive"))
      (node (ref "D211") (pin "C") (pinfunction "C_C") (pintype "passive"))
      (node (ref "D212") (pin "A") (pinfunction "A_A") (pintype "passive"))
      (node (ref "D225") (pin "C") (pinfunction "C_C") (pintype "passive"))
      (node (ref "D227") (pin "A") (pinfunction "A_A") (pintype "passive"))
      (node (ref "D238") (pin "C") (pinfunction "C_C") (pintype "passive"))
      (node (ref "D241") (pin "A") (pinfunction "A_A") (pintype "passive"))
      (node (ref "D250") (pin "C") (pinfunction "C_C") (pintype "passive"))
      (node (ref "D301") (pin "C") (pinfunction "C_C") (pintype "passive"))
      (node (ref "D311") (pin "C") (pinfunction "C_C") (pintype "passive"))
      (node (ref "D320") (pin "C") (pinfunction "C_C") (pintype "passive"))
      (node (ref "D328") (pin "C") (pinfunction "C_C") (pintype "passive"))
      (node (ref "D335") (pin "C") (pinfunction "C_C") (pintype "passive"))
      (node (ref "D341") (pin "C") (pinfunction "C_C") (pintype "passive"))
      (node (ref "D346") (pin "C") (pinfunction "C_C") (pintype "passive"))
      (node (ref "D350") (pin "C") (pinfunction "C_C") (pintype "passive"))
      (node (ref "R4") (pin "8") (pinfunction "2_8") (pintype "passive"))
    )
    (net (code "35") (name "/Q14") (class "Default")
      (node (ref "D012") (pin "A") (pinfunction "A_A") (pintype "passive"))
      (node (ref "D013") (pin "C") (pinfunction "C_C") (pintype "passive"))
      (node (ref "D026") (pin "A") (pinfunction "A_A") (pintype "passive"))
      (node (ref "D028") (pin "C") (pinfunction "C_C") (pintype "passive"))
      (node (ref "D039") (pin "A") (pinfunction "A_A") (pintype "passive"))
      (node (ref "D051") (pin "A") (pinfunction "A_A") (pintype "passive"))
      (node (ref "D102") (pin "A") (pinfunction "A_A") (pintype "passive"))
      (node (ref "D112") (pin "A") (pinfunction "A_A") (pintype "passive"))
      (node (ref "D121") (pin "A") (pinfunction "A_A") (pintype "passive"))
      (node (ref "D129") (pin "A") (pinfunction "A_A") (pintype "passive"))
      (node (ref "D136") (pin "A") (pinfunction "A_A") (pintype "passive"))
      (node (ref "D142") (pin "A") (pinfunction "A_A") (pintype "passive"))
      (node (ref "D147") (pin "A") (pinfunction "A_A") (pintype "passive"))
      (node (ref "D151") (pin "A") (pinfunction "A_A") (pintype "passive"))
      (node (ref "D154") (pin "A") (pinfunction "A_A") (pintype "passive"))
      (node (ref "D212") (pin "C") (pinfunction "C_C") (pintype "passive"))
      (node (ref "D213") (pin "A") (pinfunction "A_A") (pintype "passive"))
      (node (ref "D226") (pin "C") (pinfunction "C_C") (pintype "passive"))
      (node (ref "D228") (pin "A") (pinfunction "A_A") (pintype "passive"))
      (node (ref "D239") (pin "C") (pinfunction "C_C") (pintype "passive"))
      (node (ref "D251") (pin "C") (pinfunction "C_C") (pintype "passive"))
      (node (ref "D302") (pin "C") (pinfunction "C_C") (pintype "passive"))
      (node (ref "D312") (pin "C") (pinfunction "C_C") (pintype "passive"))
      (node (ref "D321") (pin "C") (pinfunction "C_C") (pintype "passive"))
      (node (ref "D329") (pin "C") (pinfunction "C_C") (pintype "passive"))
      (node (ref "D336") (pin "C") (pinfunction "C_C") (pintype "passive"))
      (node (ref "D342") (pin "C") (pinfunction "C_C") (pintype "passive"))
      (node (ref "D347") (pin "C") (pinfunction "C_C") (pintype "passive"))
      (node (ref "D351") (pin "C") (pinfunction "C_C") (pintype "passive"))
      (node (ref "D354") (pin "C") (pinfunction "C_C") (pintype "passive"))
      (node (ref "R4") (pin "7") (pinfunction "2_7") (pintype "passive"))
    )
    (net (code "36") (name "/Q15") (class "Default")
      (node (ref "D013") (pin "A") (pinfunction "A_A") (pintype "passive"))
      (node (ref "D014") (pin "C") (pinfunction "C_C") (pintype "passive"))
      (node (ref "D027") (pin "A") (pinfunction "A_A") (pintype "passive"))
      (node (ref "D040") (pin "A") (pinfunction "A_A") (pintype "passive"))
      (node (ref "D052") (pin "A") (pinfunction "A_A") (pintype "passive"))
      (node (ref "D103") (pin "A") (pinfunction "A_A") (pintype "passive"))
      (node (ref "D113") (pin "A") (pinfunction "A_A") (pintype "passive"))
      (node (ref "D122") (pin "A") (pinfunction "A_A") (pintype "passive"))
      (node (ref "D130") (pin "A") (pinfunction "A_A") (pintype "passive"))
      (node (ref "D137") (pin "A") (pinfunction "A_A") (pintype "passive"))
      (node (ref "D143") (pin "A") (pinfunction "A_A") (pintype "passive"))
      (node (ref "D148") (pin "A") (pinfunction "A_A") (pintype "passive"))
      (node (ref "D152") (pin "A") (pinfunction "A_A") (pintype "passive"))
      (node (ref "D155") (pin "A") (pinfunction "A_A") (pintype "passive"))
      (node (ref "D157") (pin "A") (pinfunction "A_A") (pintype "passive"))
      (node (ref "D213") (pin "C") (pinfunction "C_C") (pintype "passive"))
      (node (ref "D214") (pin "A") (pinfunction "A_A") (pintype "passive"))
      (node (ref "D227") (pin "C") (pinfunction "C_C") (pintype "passive"))
      (node (ref "D240") (pin "C") (pinfunction "C_C") (pintype "passive"))
      (node (ref "D252") (pin "C") (pinfunction "C_C") (pintype "passive"))
      (node (ref "D303") (pin "C") (pinfunction "C_C") (pintype "passive"))
      (node (ref "D313") (pin "C") (pinfunction "C_C") (pintype "passive"))
      (node (ref "D322") (pin "C") (pinfunction "C_C") (pintype "passive"))
      (node (ref "D330") (pin "C") (pinfunction "C_C") (pintype "passive"))
      (node (ref "D337") (pin "C") (pinfunction "C_C") (pintype "passive"))
      (node (ref "D343") (pin "C") (pinfunction "C_C") (pintype "passive"))
      (node (ref "D348") (pin "C") (pinfunction "C_C") (pintype "passive"))
      (node (ref "D352") (pin "C") (pinfunction "C_C") (pintype "passive"))
      (node (ref "D355") (pin "C") (pinfunction "C_C") (pintype "passive"))
      (node (ref "D357") (pin "C") (pinfunction "C_C") (pintype "passive"))
      (node (ref "R4") (pin "6") (pinfunction "2_6") (pintype "passive"))
    )
    (net (code "37") (name "/Q16") (class "Default")
      (node (ref "D014") (pin "A") (pinfunction "A_A") (pintype "passive"))
      (node (ref "D028") (pin "A") (pinfunction "A_A") (pintype "passive"))
      (node (ref "D041") (pin "A") (pinfunction "A_A") (pintype "passive"))
      (node (ref "D053") (pin "A") (pinfunction "A_A") (pintype "passive"))
      (node (ref "D104") (pin "A") (pinfunction "A_A") (pintype "passive"))
      (node (ref "D114") (pin "A") (pinfunction "A_A") (pintype "passive"))
      (node (ref "D123") (pin "A") (pinfunction "A_A") (pintype "passive"))
      (node (ref "D131") (pin "A") (pinfunction "A_A") (pintype "passive"))
      (node (ref "D138") (pin "A") (pinfunction "A_A") (pintype "passive"))
      (node (ref "D144") (pin "A") (pinfunction "A_A") (pintype "passive"))
      (node (ref "D149") (pin "A") (pinfunction "A_A") (pintype "passive"))
      (node (ref "D153") (pin "A") (pinfunction "A_A") (pintype "passive"))
      (node (ref "D156") (pin "A") (pinfunction "A_A") (pintype "passive"))
      (node (ref "D158") (pin "A") (pinfunction "A_A") (pintype "passive"))
      (node (ref "D159") (pin "A") (pinfunction "A_A") (pintype "passive"))
      (node (ref "D214") (pin "C") (pinfunction "C_C") (pintype "passive"))
      (node (ref "D228") (pin "C") (pinfunction "C_C") (pintype "passive"))
      (node (ref "D241") (pin "C") (pinfunction "C_C") (pintype "passive"))
      (node (ref "D253") (pin "C") (pinfunction "C_C") (pintype "passive"))
      (node (ref "D304") (pin "C") (pinfunction "C_C") (pintype "passive"))
      (node (ref "D314") (pin "C") (pinfunction "C_C") (pintype "passive"))
      (node (ref "D323") (pin "C") (pinfunction "C_C") (pintype "passive"))
      (node (ref "D331") (pin "C") (pinfunction "C_C") (pintype "passive"))
      (node (ref "D338") (pin "C") (pinfunction "C_C") (pintype "passive"))
      (node (ref "D344") (pin "C") (pinfunction "C_C") (pintype "passive"))
      (node (ref "D349") (pin "C") (pinfunction "C_C") (pintype "passive"))
      (node (ref "D353") (pin "C") (pinfunction "C_C") (pintype "passive"))
      (node (ref "D356") (pin "C") (pinfunction "C_C") (pintype "passive"))
      (node (ref "D358") (pin "C") (pinfunction "C_C") (pintype "passive"))
      (node (ref "D359") (pin "C") (pinfunction "C_C") (pintype "passive"))
      (node (ref "R4") (pin "5") (pinfunction "2_5") (pintype "passive"))
    )
    (net (code "38") (name "/RESET") (class "Default")
      (node (ref "C502") (pin "1") (pinfunction "1_1") (pintype "passive"))
      (node (ref "J003") (pin "1") (pinfunction "1_1") (pintype "passive"))
      (node (ref "R606") (pin "5") (pinfunction "2_5") (pintype "passive"))
      (node (ref "S429") (pin "P$2") (pinfunction "2_P$2") (pintype "bidirectional"))
      (node (ref "U401") (pin "29") (pinfunction "PC6(/RESET)_29") (pintype "bidirectional"))
    )
    (net (code "39") (name "/USBD+") (class "Default")
      (node (ref "J002") (pin "1") (pinfunction "1_1") (pintype "passive"))
      (node (ref "U501") (pin "15") (pinfunction "USBDP_15") (pintype "bidirectional"))
    )
    (net (code "40") (name "/USBD-") (class "Default")
      (node (ref "J002") (pin "2") (pinfunction "2_2") (pintype "passive"))
      (node (ref "U501") (pin "16") (pinfunction "USBDM_16") (pintype "bidirectional"))
    )
    (net (code "41") (name "/USB_TX") (class "Default")
      (node (ref "SJ1") (pin "3") (pinfunction "3_3") (pintype "passive"))
      (node (ref "U501") (pin "1") (pinfunction "TXD_1") (pintype "output"))
      (node (ref "U602") (pin "1") (pinfunction "I1_1") (pintype "bidirectional"))
    )
    (net (code "42") (name "/XTAL1") (class "Default")
      (node (ref "C407") (pin "2") (pinfunction "2_2") (pintype "passive"))
      (node (ref "U401") (pin "7") (pinfunction "PB6(XTAL1/TOSC1)_7") (pintype "bidirectional"))
      (node (ref "Y401") (pin "1") (pinfunction "1_1") (pintype "bidirectional"))
    )
    (net (code "43") (name "/XTAL2") (class "Default")
      (node (ref "C408") (pin "2") (pinfunction "2_2") (pintype "passive"))
      (node (ref "U401") (pin "8") (pinfunction "PB7(XTAL2/TOSC2)_8") (pintype "bidirectional"))
      (node (ref "Y401") (pin "3") (pinfunction "2_3") (pintype "bidirectional"))
    )
    (net (code "44") (name "GND") (class "Default")
      (node (ref "C010") (pin "2") (pinfunction "2_2") (pintype "passive"))
      (node (ref "C407") (pin "1") (pinfunction "1_1") (pintype "passive"))
      (node (ref "C408") (pin "1") (pinfunction "1_1") (pintype "passive"))
      (node (ref "C418") (pin "1") (pinfunction "1_1") (pintype "passive"))
      (node (ref "C420") (pin "2") (pinfunction "2_2") (pintype "passive"))
      (node (ref "J002") (pin "4") (pinfunction "4_4") (pintype "passive"))
      (node (ref "J003") (pin "3") (pinfunction "3_3") (pintype "passive"))
      (node (ref "J402") (pin "1") (pinfunction "GND1_1") (pintype "bidirectional"))
      (node (ref "J402") (pin "5") (pinfunction "GND2_5") (pintype "bidirectional"))
      (node (ref "J404") (pin "1") (pinfunction "GND1_1") (pintype "bidirectional"))
      (node (ref "J404") (pin "5") (pinfunction "GND2_5") (pintype "bidirectional"))
      (node (ref "S429") (pin "P$1") (pinfunction "1_P$1") (pintype "bidirectional"))
      (node (ref "S429") (pin "P$3") (pinfunction "1_P$3") (pintype "bidirectional"))
      (node (ref "U401") (pin "21") (pinfunction "GND_21") (pintype "bidirectional"))
      (node (ref "U401") (pin "3") (pinfunction "GND_3") (pintype "bidirectional"))
      (node (ref "U401") (pin "5") (pinfunction "AGND_5") (pintype "bidirectional"))
      (node (ref "U501") (pin "18") (pinfunction "GND18_18") (pintype "power_in"))
      (node (ref "U501") (pin "21") (pinfunction "GND21_21") (pintype "power_in"))
      (node (ref "U501") (pin "25") (pinfunction "AGND_25") (pintype "power_in"))
      (node (ref "U501") (pin "26") (pinfunction "TEST_26") (pintype "input"))
      (node (ref "U501") (pin "7") (pinfunction "GND7_7") (pintype "power_in"))
      (node (ref "U602") (pin "2") (pinfunction "GND_2") (pintype "bidirectional"))
      (node (ref "Y401") (pin "2") (pinfunction "1_2") (pintype "bidirectional"))
      (node (ref "Y401") (pin "4") (pinfunction "1_4") (pintype "bidirectional"))
    )
    (net (code "45") (name "Net-(D501-PadC)") (class "Default")
      (node (ref "D501") (pin "C") (pinfunction "C_C") (pintype "passive"))
      (node (ref "R501") (pin "2") (pinfunction "2_2") (pintype "passive"))
    )
    (net (code "46") (name "Net-(D502-PadC)") (class "Default")
      (node (ref "D502") (pin "C") (pinfunction "C_C") (pintype "passive"))
      (node (ref "R502") (pin "2") (pinfunction "2_2") (pintype "passive"))
    )
    (net (code "47") (name "Net-(U401-AREF)") (class "Default")
      (node (ref "C420") (pin "1") (pinfunction "1_1") (pintype "passive"))
      (node (ref "U401") (pin "20") (pinfunction "AREF_20") (pintype "bidirectional"))
    )
    (net (code "48") (name "Net-(U501-DTR)") (class "Default")
      (node (ref "C502") (pin "2") (pinfunction "2_2") (pintype "passive"))
      (node (ref "U501") (pin "2") (pinfunction "DTR_2") (pintype "output"))
    )
    (net (code "49") (name "Net-(U501-RXLED)") (class "Default")
      (node (ref "R502") (pin "1") (pinfunction "1_1") (pintype "passive"))
      (node (ref "U501") (pin "22") (pinfunction "RXLED_22") (pintype "input"))
    )
    (net (code "50") (name "Net-(U501-TXLED)") (class "Default")
      (node (ref "R501") (pin "1") (pinfunction "1_1") (pintype "passive"))
      (node (ref "U501") (pin "23") (pinfunction "TXLED_23") (pintype "input"))
    )
    (net (code "51") (name "VCC") (class "Default")
      (node (ref "C010") (pin "1") (pinfunction "1_1") (pintype "passive"))
      (node (ref "C418") (pin "2") (pinfunction "2_2") (pintype "passive"))
      (node (ref "D501") (pin "A") (pinfunction "A_A") (pintype "passive"))
      (node (ref "D502") (pin "A") (pinfunction "A_A") (pintype "passive"))
      (node (ref "J002") (pin "3") (pinfunction "3_3") (pintype "passive"))
      (node (ref "J003") (pin "2") (pinfunction "2_2") (pintype "passive"))
      (node (ref "J402") (pin "2") (pinfunction "VCC_2") (pintype "bidirectional"))
      (node (ref "J404") (pin "2") (pinfunction "VCC_2") (pintype "bidirectional"))
      (node (ref "R606") (pin "1") (pinfunction "1_1") (pintype "passive"))
      (node (ref "R606") (pin "4") (pinfunction "1_4") (pintype "passive"))
      (node (ref "U401") (pin "18") (pinfunction "AVCC_18") (pintype "bidirectional"))
      (node (ref "U401") (pin "4") (pinfunction "VCC_4") (pintype "bidirectional"))
      (node (ref "U401") (pin "6") (pinfunction "VCC_6") (pintype "bidirectional"))
      (node (ref "U501") (pin "20") (pinfunction "VCC_20") (pintype "power_in"))
      (node (ref "U501") (pin "4") (pinfunction "VCCIO_4") (pintype "power_in"))
      (node (ref "U602") (pin "5") (pinfunction "VCC_5") (pintype "bidirectional"))
    )
    (net (code "52") (name "unconnected-(U401-ADC6-Pad19)") (class "Default")
      (node (ref "U401") (pin "19") (pinfunction "ADC6_19") (pintype "bidirectional"))
    )
    (net (code "53") (name "unconnected-(U401-ADC7-Pad22)") (class "Default")
      (node (ref "U401") (pin "22") (pinfunction "ADC7_22") (pintype "bidirectional"))
    )
    (net (code "54") (name "unconnected-(U501-3V3OUT-Pad17)") (class "Default")
      (node (ref "U501") (pin "17") (pinfunction "3V3OUT_17") (pintype "output"))
    )
    (net (code "55") (name "unconnected-(U501-CTS-Pad11)") (class "Default")
      (node (ref "U501") (pin "11") (pinfunction "CTS_11") (pintype "input"))
    )
    (net (code "56") (name "unconnected-(U501-DCD-Pad10)") (class "Default")
      (node (ref "U501") (pin "10") (pinfunction "DCD_10") (pintype "input"))
    )
    (net (code "57") (name "unconnected-(U501-DSR-Pad9)") (class "Default")
      (node (ref "U501") (pin "9") (pinfunction "DSR_9") (pintype "input"))
    )
    (net (code "58") (name "unconnected-(U501-OSCI-Pad27)") (class "Default")
      (node (ref "U501") (pin "27") (pinfunction "OSCI_27") (pintype "input"))
    )
    (net (code "59") (name "unconnected-(U501-OSCO-Pad28)") (class "Default")
      (node (ref "U501") (pin "28") (pinfunction "OSCO_28") (pintype "output"))
    )
    (net (code "60") (name "unconnected-(U501-PWREN-Pad14)") (class "Default")
      (node (ref "U501") (pin "14") (pinfunction "PWREN_14") (pintype "input"))
    )
    (net (code "61") (name "unconnected-(U501-RESET-Pad19)") (class "Default")
      (node (ref "U501") (pin "19") (pinfunction "RESET_19") (pintype "input"))
    )
    (net (code "62") (name "unconnected-(U501-RI-Pad6)") (class "Default")
      (node (ref "U501") (pin "6") (pinfunction "RI_6") (pintype "input"))
    )
    (net (code "63") (name "unconnected-(U501-RTS-Pad3)") (class "Default")
      (node (ref "U501") (pin "3") (pinfunction "RTS_3") (pintype "output"))
    )
    (net (code "64") (name "unconnected-(U501-SLEEP-Pad12)") (class "Default")
      (node (ref "U501") (pin "12") (pinfunction "SLEEP_12") (pintype "input"))
    )
    (net (code "65") (name "unconnected-(U501-TXDEN-Pad13)") (class "Default")
      (node (ref "U501") (pin "13") (pinfunction "TXDEN_13") (pintype "input"))
    )
  )
)
